# shelves_v05.net
KiCad netlist of a schematic drawn in EAGLE
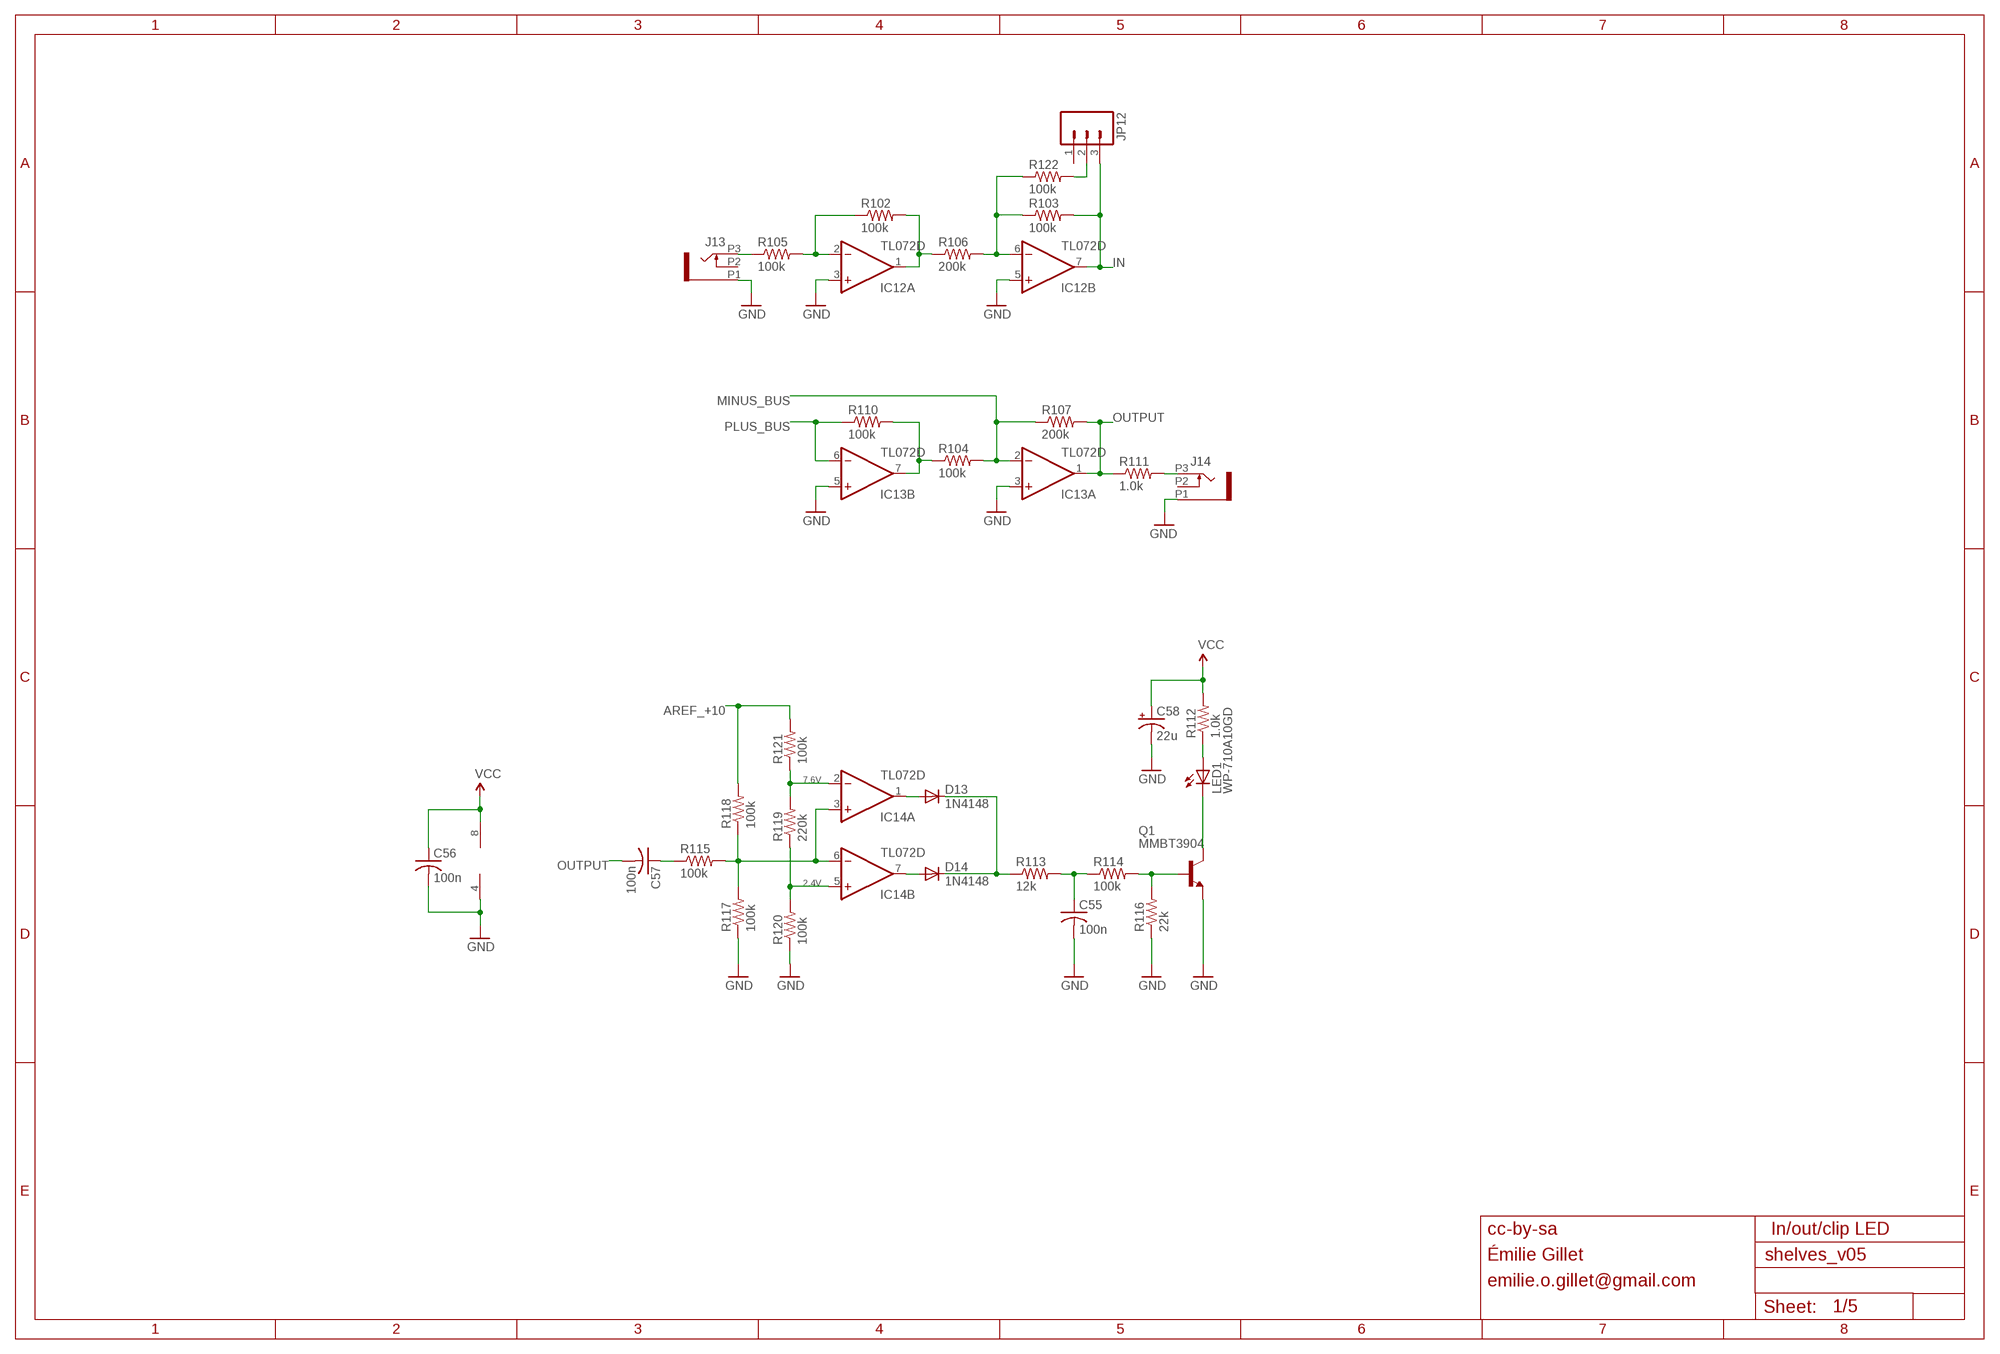
[diagram p0: schematic, sheet 1]
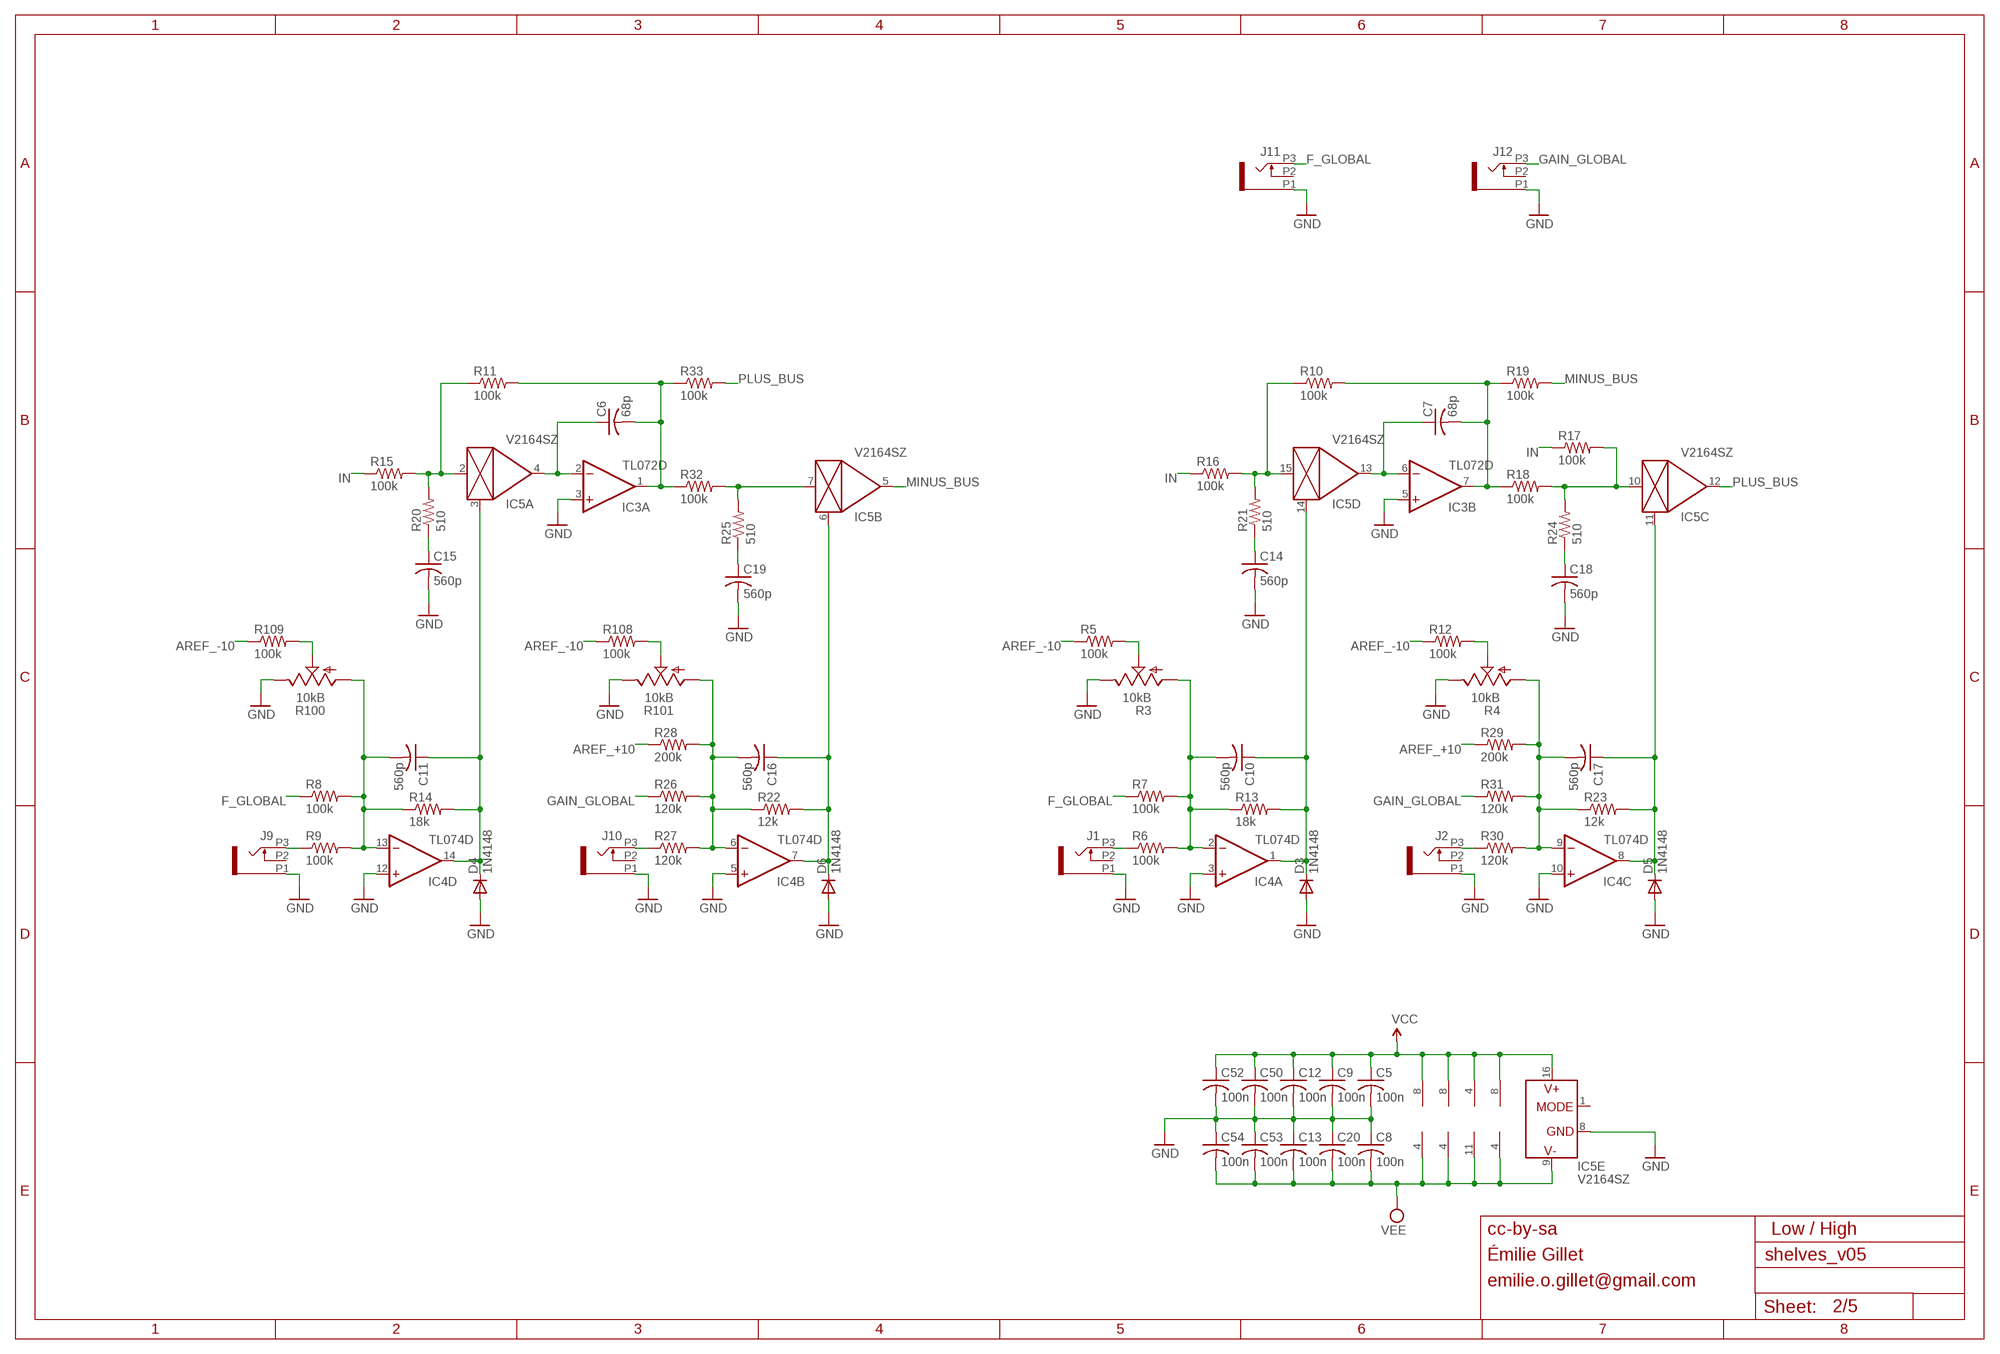
[diagram p1: schematic, sheet 2]
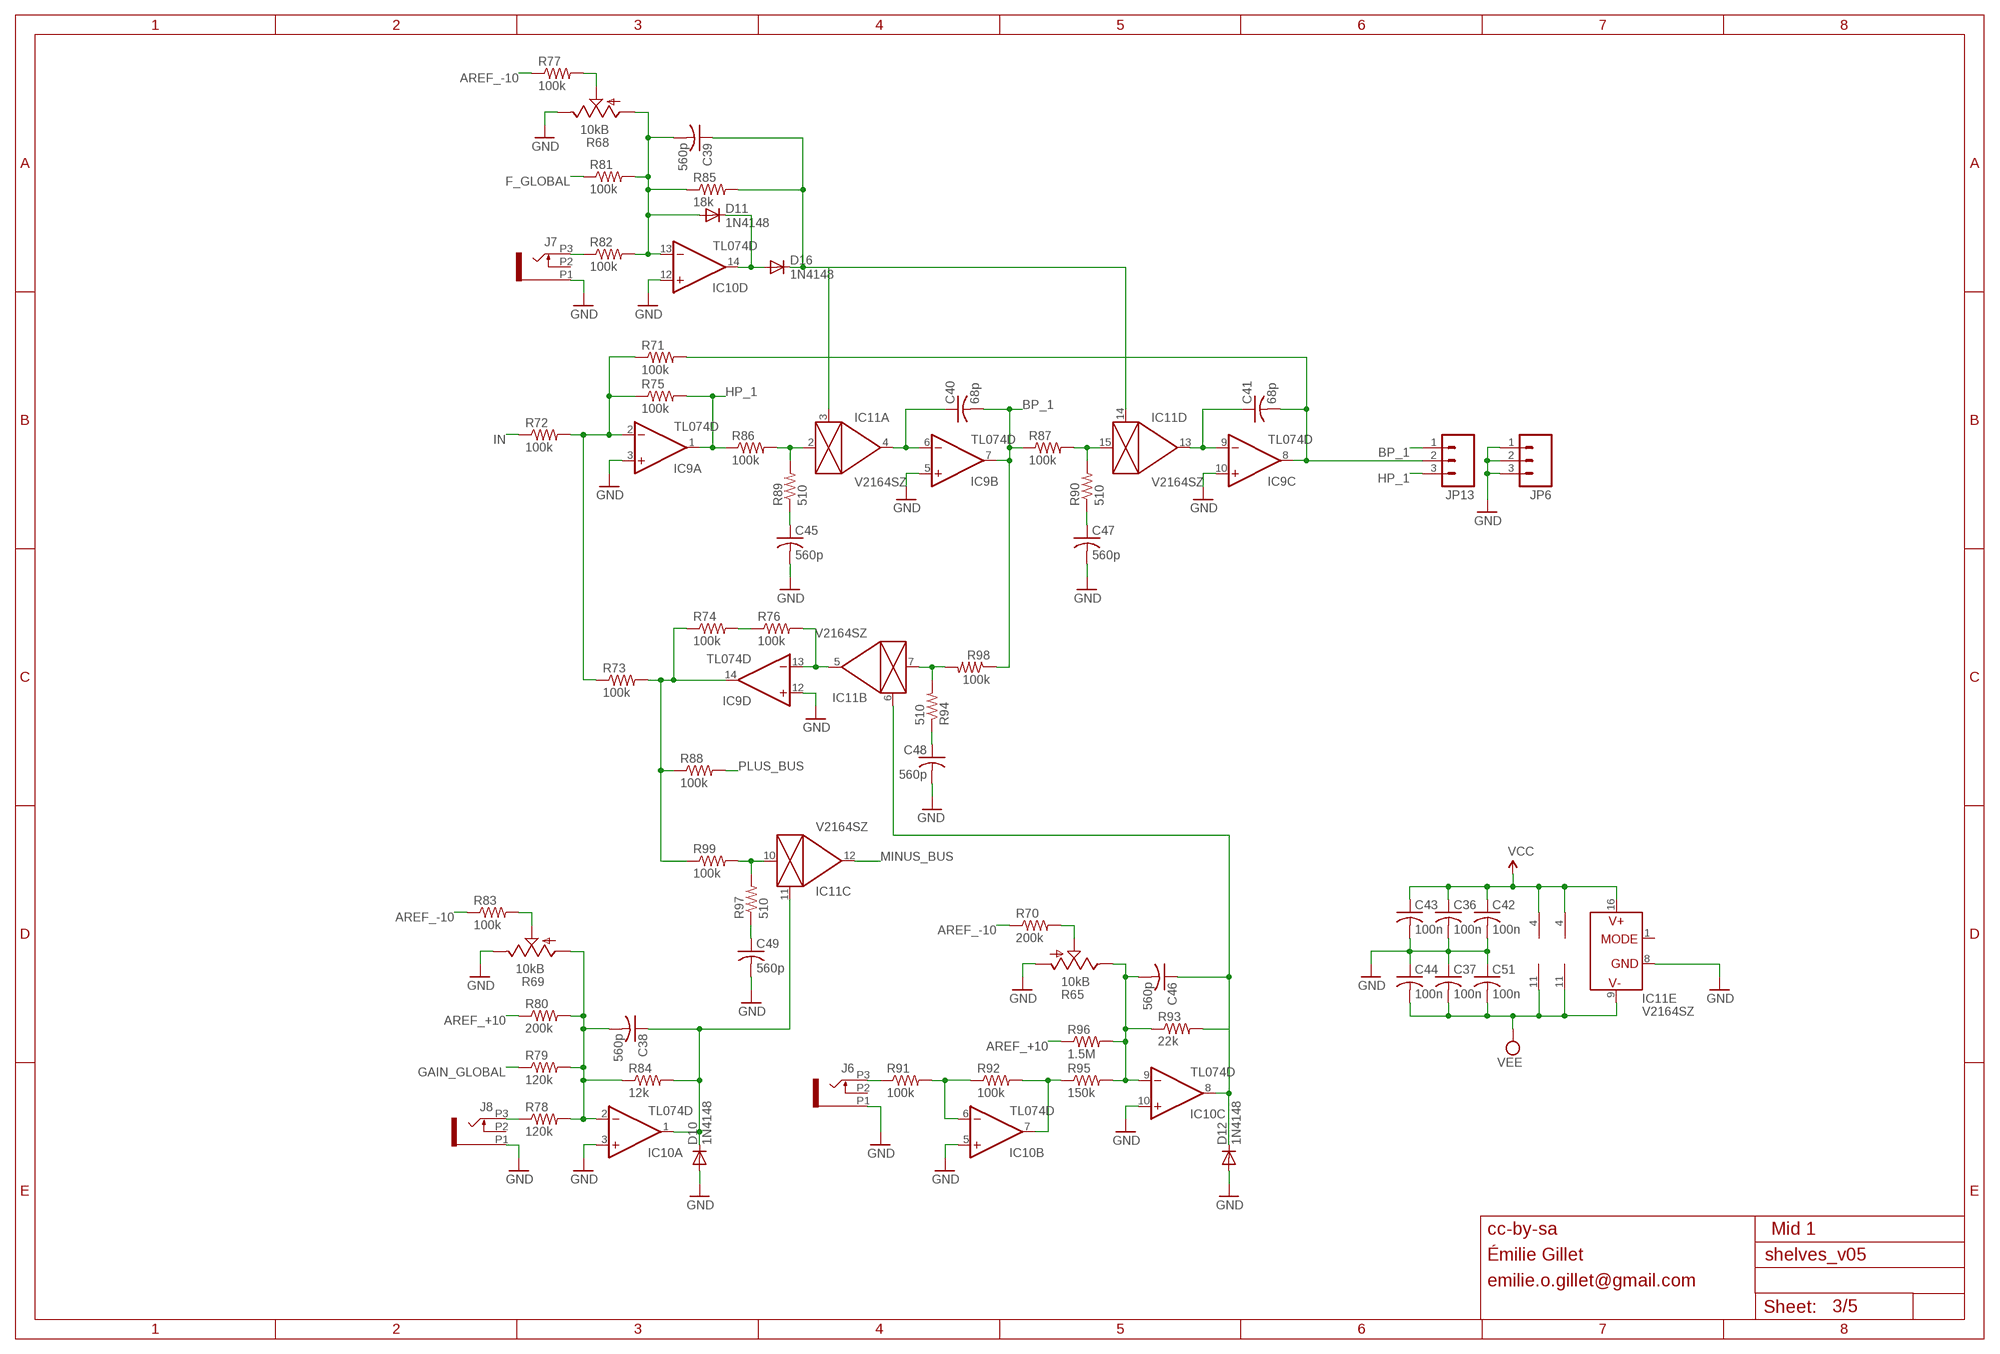
[diagram p2: schematic, sheet 3]
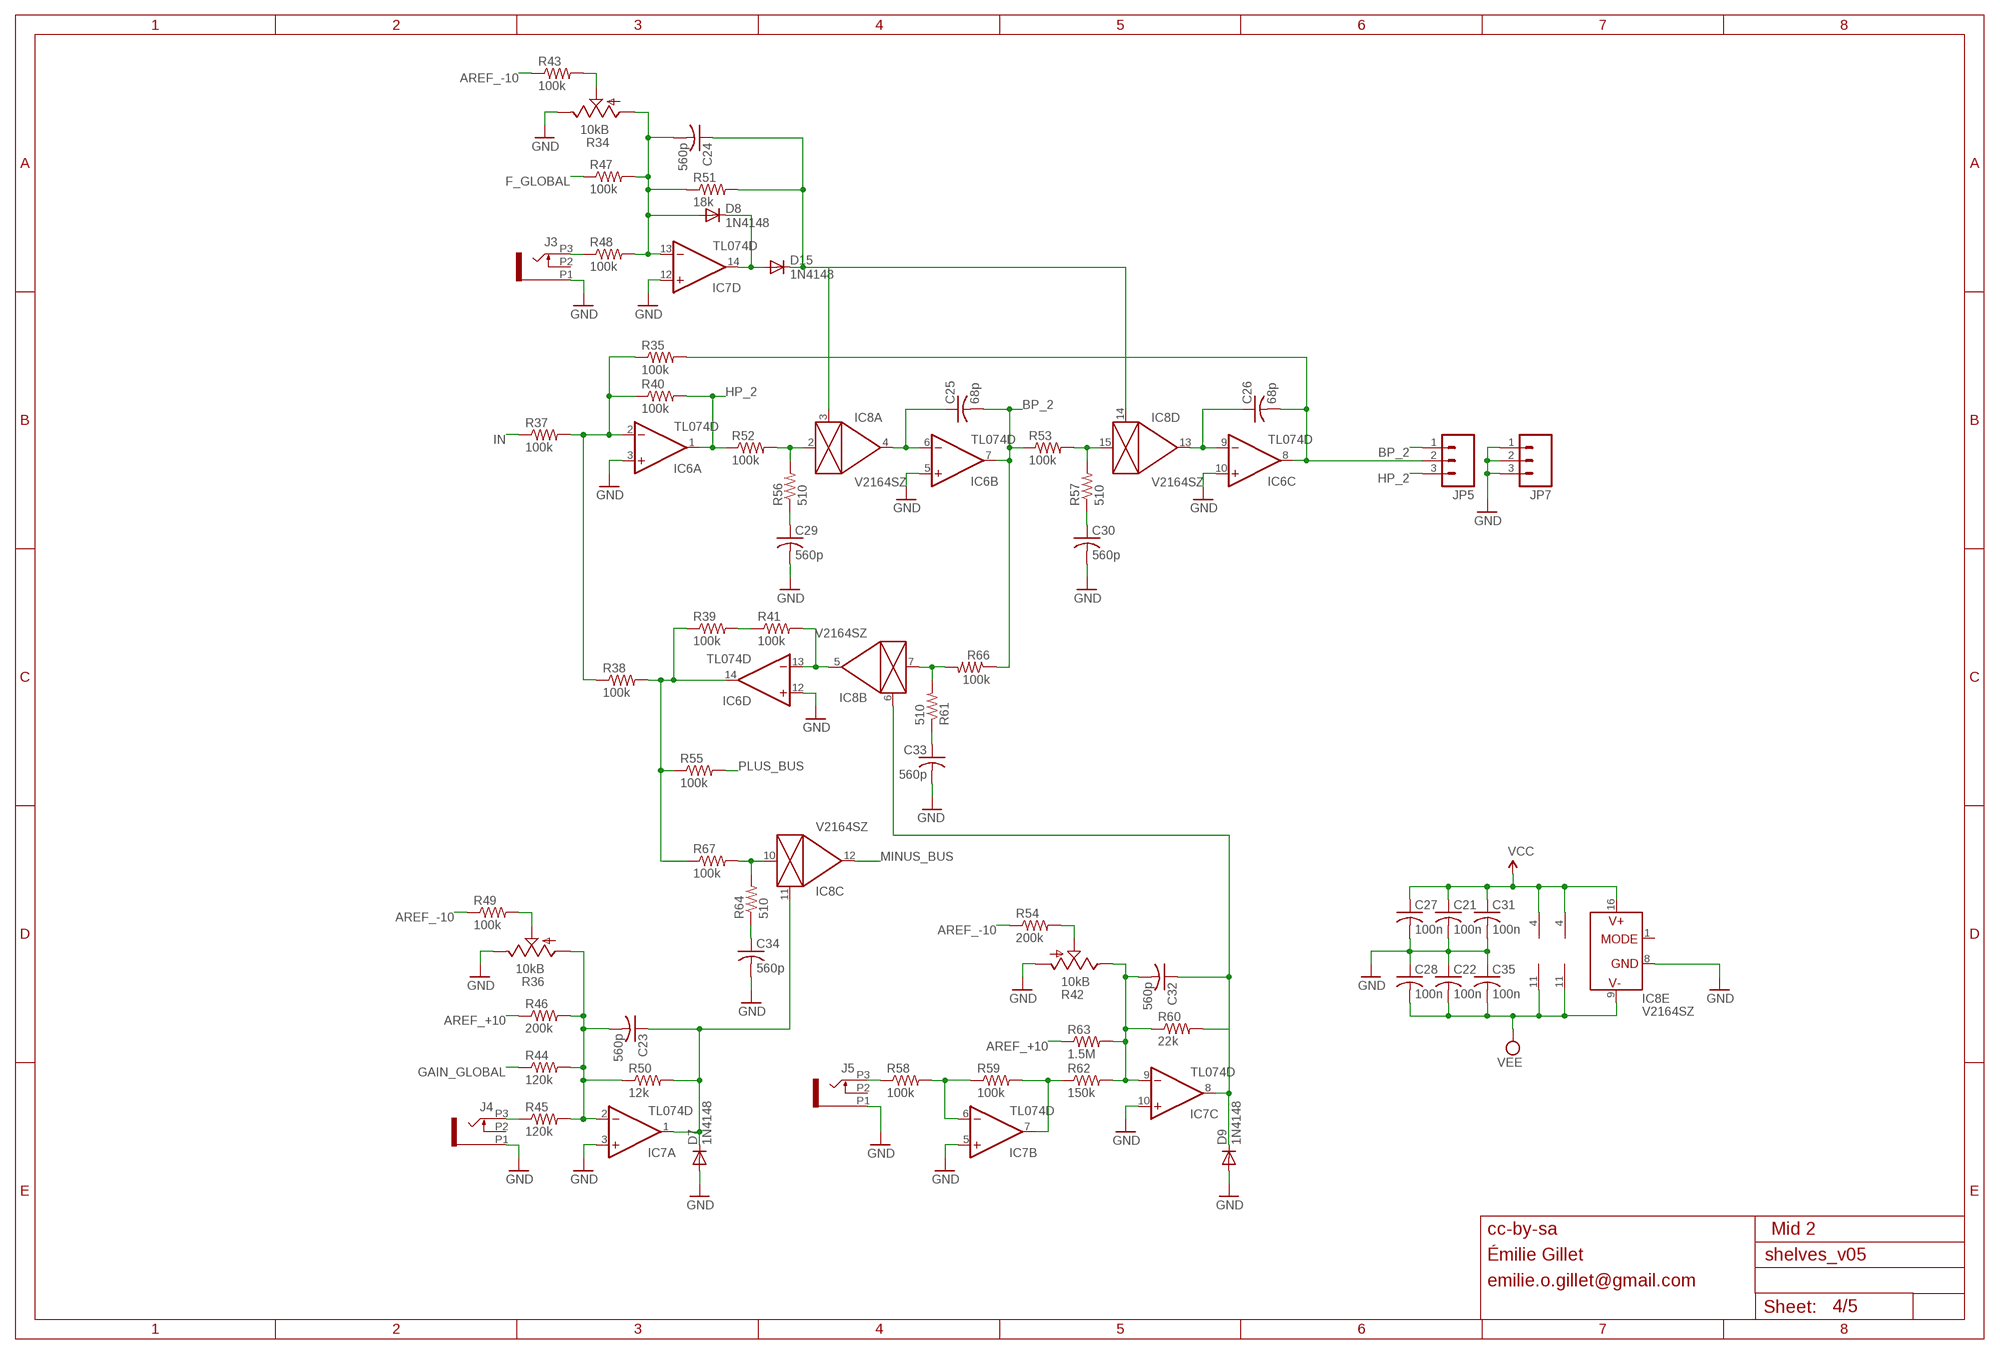
[diagram p3: schematic, sheet 4]
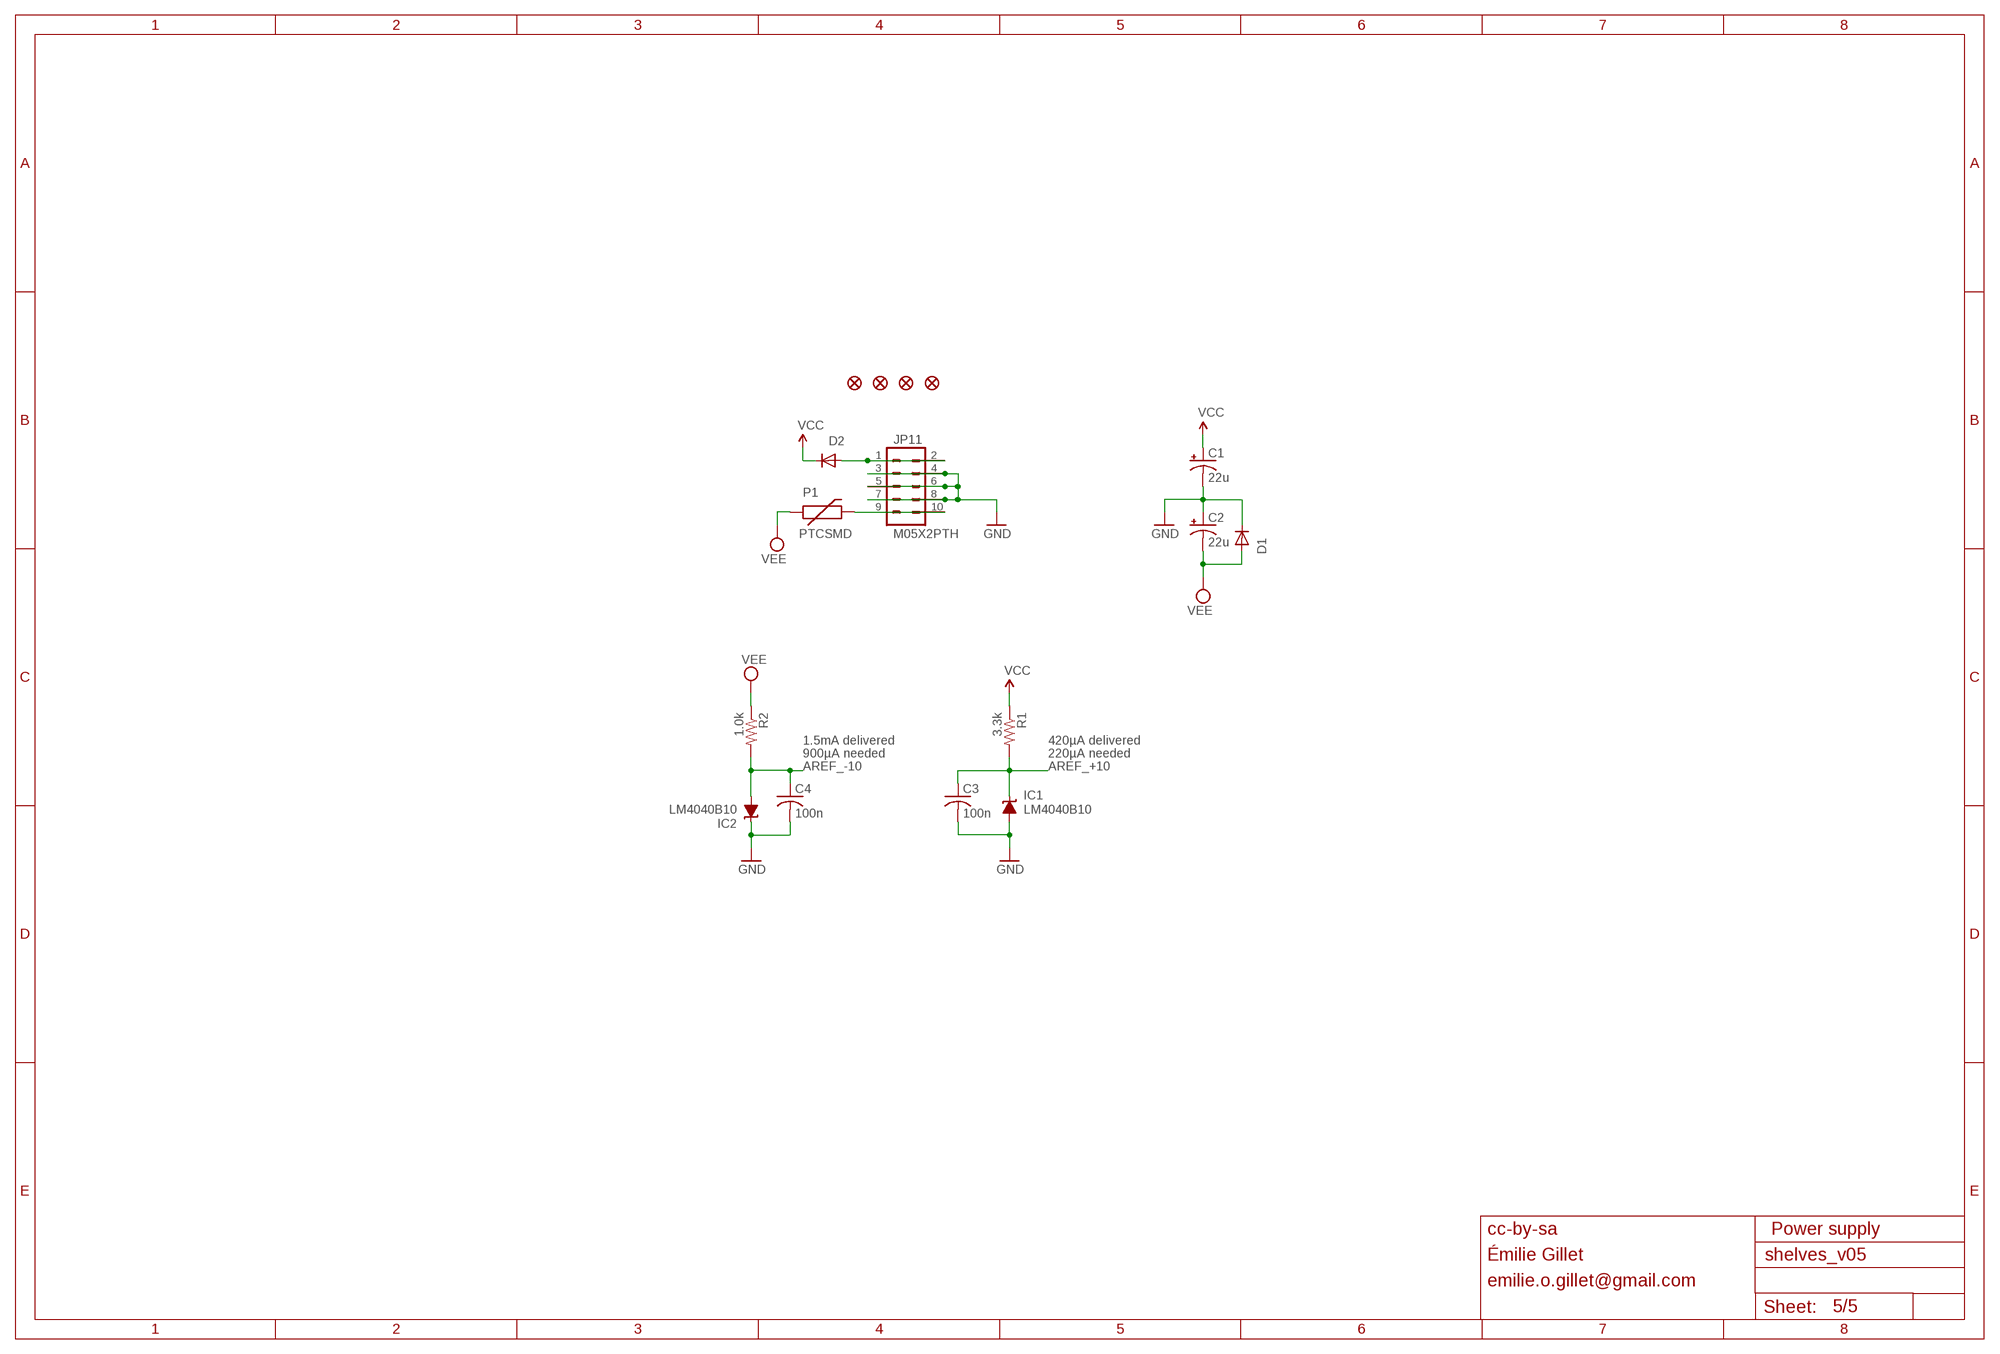
[diagram p4: schematic, sheet 5]

(export (version "E")
  (design (tool "Eeschema 10.0.6"))
  (components
    (comp (ref "C36")
      (value "100n")
      (footprint "eagle-import:C0603")
      (libsource (lib "eagle-import") (part "C-USC0603"))
    )
    (comp (ref "C37")
      (value "100n")
      (footprint "eagle-import:C0603")
      (libsource (lib "eagle-import") (part "C-USC0603"))
    )
    (comp (ref "C38")
      (value "560p")
      (footprint "eagle-import:C0603")
      (libsource (lib "eagle-import") (part "C-USC0603"))
    )
    (comp (ref "C39")
      (value "560p")
      (footprint "eagle-import:C0603")
      (libsource (lib "eagle-import") (part "C-USC0603"))
    )
    (comp (ref "C40")
      (value "68p")
      (footprint "eagle-import:C0603")
      (libsource (lib "eagle-import") (part "C-USC0603"))
    )
    (comp (ref "C41")
      (value "68p")
      (footprint "eagle-import:C0603")
      (libsource (lib "eagle-import") (part "C-USC0603"))
    )
    (comp (ref "C42")
      (value "100n")
      (footprint "eagle-import:C0603")
      (libsource (lib "eagle-import") (part "C-USC0603"))
    )
    (comp (ref "C43")
      (value "100n")
      (footprint "eagle-import:C0603")
      (libsource (lib "eagle-import") (part "C-USC0603"))
    )
    (comp (ref "C44")
      (value "100n")
      (footprint "eagle-import:C0603")
      (libsource (lib "eagle-import") (part "C-USC0603"))
    )
    (comp (ref "C45")
      (value "560p")
      (footprint "eagle-import:C0603")
      (libsource (lib "eagle-import") (part "C-USC0603"))
    )
    (comp (ref "C46")
      (value "560p")
      (footprint "eagle-import:C0603")
      (libsource (lib "eagle-import") (part "C-USC0603"))
    )
    (comp (ref "C47")
      (value "560p")
      (footprint "eagle-import:C0603")
      (libsource (lib "eagle-import") (part "C-USC0603"))
    )
    (comp (ref "C48")
      (value "560p")
      (footprint "eagle-import:C0603")
      (libsource (lib "eagle-import") (part "C-USC0603"))
    )
    (comp (ref "C49")
      (value "560p")
      (footprint "eagle-import:C0603")
      (libsource (lib "eagle-import") (part "C-USC0603"))
    )
    (comp (ref "C51")
      (value "100n")
      (footprint "eagle-import:C0603")
      (libsource (lib "eagle-import") (part "C-USC0603"))
    )
    (comp (ref "D10")
      (value "1N4148")
      (footprint "eagle-import:SOD323-W")
      (libsource (lib "eagle-import") (part "DIODE-SOD323-W"))
    )
    (comp (ref "D11")
      (value "1N4148")
      (footprint "eagle-import:SOD323-W")
      (libsource (lib "eagle-import") (part "DIODE-SOD323-W"))
    )
    (comp (ref "D12")
      (value "1N4148")
      (footprint "eagle-import:SOD323-W")
      (libsource (lib "eagle-import") (part "DIODE-SOD323-W"))
    )
    (comp (ref "D16")
      (value "1N4148")
      (footprint "eagle-import:SOD323-W")
      (libsource (lib "eagle-import") (part "DIODE-SOD323-W"))
    )
    (comp (ref "IC9")
      (value "TL074D")
      (footprint "eagle-import:SO14")
      (libsource (lib "eagle-import") (part "TL074D"))
    )
    (comp (ref "IC10")
      (value "TL074D")
      (footprint "eagle-import:SO14")
      (libsource (lib "eagle-import") (part "TL074D"))
    )
    (comp (ref "IC11")
      (value "V2164SZ")
      (footprint "eagle-import:SOIC16N")
      (libsource (lib "eagle-import") (part "SSM2164S"))
    )
    (comp (ref "J6")
      (value "PJ301_THONKICONN6")
      (footprint "eagle-import:WQP_PJ_301M6")
      (libsource (lib "eagle-import") (part "PJ301_THONKICONN6"))
    )
    (comp (ref "J7")
      (value "PJ301_THONKICONN6")
      (footprint "eagle-import:WQP_PJ_301M6")
      (libsource (lib "eagle-import") (part "PJ301_THONKICONN6"))
    )
    (comp (ref "J8")
      (value "PJ301_THONKICONN6")
      (footprint "eagle-import:WQP_PJ_301M6")
      (libsource (lib "eagle-import") (part "PJ301_THONKICONN6"))
    )
    (comp (ref "JP6")
      (value "M03PTH")
      (footprint "eagle-import:1X03")
      (libsource (lib "eagle-import") (part "M03PTH"))
    )
    (comp (ref "JP13")
      (value "M03PTH")
      (footprint "eagle-import:1X03")
      (libsource (lib "eagle-import") (part "M03PTH"))
    )
    (comp (ref "R65")
      (value "10kB")
      (footprint "eagle-import:ALPS_POT_VERTICAL")
      (libsource (lib "eagle-import") (part "POT_USVERTICAL"))
    )
    (comp (ref "R68")
      (value "10kB")
      (footprint "eagle-import:ALPS_POT_VERTICAL_PS")
      (libsource (lib "eagle-import") (part "POT_USVERTICAL_PS"))
    )
    (comp (ref "R69")
      (value "10kB")
      (footprint "eagle-import:ALPS_POT_VERTICAL_PS")
      (libsource (lib "eagle-import") (part "POT_USVERTICAL_PS"))
    )
    (comp (ref "R70")
      (value "200k")
      (footprint "eagle-import:R0603")
      (libsource (lib "eagle-import") (part "R-US_R0603"))
    )
    (comp (ref "R71")
      (value "100k")
      (footprint "eagle-import:R0603")
      (libsource (lib "eagle-import") (part "R-US_R0603"))
    )
    (comp (ref "R72")
      (value "100k")
      (footprint "eagle-import:R0603")
      (libsource (lib "eagle-import") (part "R-US_R0603"))
    )
    (comp (ref "R73")
      (value "100k")
      (footprint "eagle-import:R0603")
      (libsource (lib "eagle-import") (part "R-US_R0603"))
    )
    (comp (ref "R74")
      (value "100k")
      (footprint "eagle-import:R0603")
      (libsource (lib "eagle-import") (part "R-US_R0603"))
    )
    (comp (ref "R75")
      (value "100k")
      (footprint "eagle-import:R0603")
      (libsource (lib "eagle-import") (part "R-US_R0603"))
    )
    (comp (ref "R76")
      (value "100k")
      (footprint "eagle-import:R0603")
      (libsource (lib "eagle-import") (part "R-US_R0603"))
    )
    (comp (ref "R77")
      (value "100k")
      (footprint "eagle-import:R0603")
      (libsource (lib "eagle-import") (part "R-US_R0603"))
    )
    (comp (ref "R78")
      (value "120k")
      (footprint "eagle-import:R0603")
      (libsource (lib "eagle-import") (part "R-US_R0603"))
    )
    (comp (ref "R79")
      (value "120k")
      (footprint "eagle-import:R0603")
      (libsource (lib "eagle-import") (part "R-US_R0603"))
    )
    (comp (ref "R80")
      (value "200k")
      (footprint "eagle-import:R0603")
      (libsource (lib "eagle-import") (part "R-US_R0603"))
    )
    (comp (ref "R81")
      (value "100k")
      (footprint "eagle-import:R0603")
      (libsource (lib "eagle-import") (part "R-US_R0603"))
    )
    (comp (ref "R82")
      (value "100k")
      (footprint "eagle-import:R0603")
      (libsource (lib "eagle-import") (part "R-US_R0603"))
    )
    (comp (ref "R83")
      (value "100k")
      (footprint "eagle-import:R0603")
      (libsource (lib "eagle-import") (part "R-US_R0603"))
    )
    (comp (ref "R84")
      (value "12k")
      (footprint "eagle-import:R0603")
      (libsource (lib "eagle-import") (part "R-US_R0603"))
    )
    (comp (ref "R85")
      (value "18k")
      (footprint "eagle-import:R0603")
      (libsource (lib "eagle-import") (part "R-US_R0603"))
    )
    (comp (ref "R86")
      (value "100k")
      (footprint "eagle-import:R0603")
      (libsource (lib "eagle-import") (part "R-US_R0603"))
    )
    (comp (ref "R87")
      (value "100k")
      (footprint "eagle-import:R0603")
      (libsource (lib "eagle-import") (part "R-US_R0603"))
    )
    (comp (ref "R88")
      (value "100k")
      (footprint "eagle-import:R0603")
      (libsource (lib "eagle-import") (part "R-US_R0603"))
    )
    (comp (ref "R89")
      (value "510")
      (footprint "eagle-import:R0603")
      (libsource (lib "eagle-import") (part "R-US_R0603"))
    )
    (comp (ref "R90")
      (value "510")
      (footprint "eagle-import:R0603")
      (libsource (lib "eagle-import") (part "R-US_R0603"))
    )
    (comp (ref "R91")
      (value "100k")
      (footprint "eagle-import:R0603")
      (libsource (lib "eagle-import") (part "R-US_R0603"))
    )
    (comp (ref "R92")
      (value "100k")
      (footprint "eagle-import:R0603")
      (libsource (lib "eagle-import") (part "R-US_R0603"))
    )
    (comp (ref "R93")
      (value "22k")
      (footprint "eagle-import:R0603")
      (libsource (lib "eagle-import") (part "R-US_R0603"))
    )
    (comp (ref "R94")
      (value "510")
      (footprint "eagle-import:R0603")
      (libsource (lib "eagle-import") (part "R-US_R0603"))
    )
    (comp (ref "R95")
      (value "150k")
      (footprint "eagle-import:R0603")
      (libsource (lib "eagle-import") (part "R-US_R0603"))
    )
    (comp (ref "R96")
      (value "1.5M")
      (footprint "eagle-import:R0603")
      (libsource (lib "eagle-import") (part "R-US_R0603"))
    )
    (comp (ref "R97")
      (value "510")
      (footprint "eagle-import:R0603")
      (libsource (lib "eagle-import") (part "R-US_R0603"))
    )
    (comp (ref "R98")
      (value "100k")
      (footprint "eagle-import:R0603")
      (libsource (lib "eagle-import") (part "R-US_R0603"))
    )
    (comp (ref "R99")
      (value "100k")
      (footprint "eagle-import:R0603")
      (libsource (lib "eagle-import") (part "R-US_R0603"))
    )
    (comp (ref "C5")
      (value "100n")
      (footprint "eagle-import:C0603")
      (libsource (lib "eagle-import") (part "C-USC0603"))
    )
    (comp (ref "C6")
      (value "68p")
      (footprint "eagle-import:C0603")
      (libsource (lib "eagle-import") (part "C-USC0603"))
    )
    (comp (ref "C7")
      (value "68p")
      (footprint "eagle-import:C0603")
      (libsource (lib "eagle-import") (part "C-USC0603"))
    )
    (comp (ref "C8")
      (value "100n")
      (footprint "eagle-import:C0603")
      (libsource (lib "eagle-import") (part "C-USC0603"))
    )
    (comp (ref "C9")
      (value "100n")
      (footprint "eagle-import:C0603")
      (libsource (lib "eagle-import") (part "C-USC0603"))
    )
    (comp (ref "C10")
      (value "560p")
      (footprint "eagle-import:C0603")
      (libsource (lib "eagle-import") (part "C-USC0603"))
    )
    (comp (ref "C11")
      (value "560p")
      (footprint "eagle-import:C0603")
      (libsource (lib "eagle-import") (part "C-USC0603"))
    )
    (comp (ref "C12")
      (value "100n")
      (footprint "eagle-import:C0603")
      (libsource (lib "eagle-import") (part "C-USC0603"))
    )
    (comp (ref "C13")
      (value "100n")
      (footprint "eagle-import:C0603")
      (libsource (lib "eagle-import") (part "C-USC0603"))
    )
    (comp (ref "C14")
      (value "560p")
      (footprint "eagle-import:C0603")
      (libsource (lib "eagle-import") (part "C-USC0603"))
    )
    (comp (ref "C15")
      (value "560p")
      (footprint "eagle-import:C0603")
      (libsource (lib "eagle-import") (part "C-USC0603"))
    )
    (comp (ref "C16")
      (value "560p")
      (footprint "eagle-import:C0603")
      (libsource (lib "eagle-import") (part "C-USC0603"))
    )
    (comp (ref "C17")
      (value "560p")
      (footprint "eagle-import:C0603")
      (libsource (lib "eagle-import") (part "C-USC0603"))
    )
    (comp (ref "C18")
      (value "560p")
      (footprint "eagle-import:C0603")
      (libsource (lib "eagle-import") (part "C-USC0603"))
    )
    (comp (ref "C19")
      (value "560p")
      (footprint "eagle-import:C0603")
      (libsource (lib "eagle-import") (part "C-USC0603"))
    )
    (comp (ref "C20")
      (value "100n")
      (footprint "eagle-import:C0603")
      (libsource (lib "eagle-import") (part "C-USC0603"))
    )
    (comp (ref "C50")
      (value "100n")
      (footprint "eagle-import:C0603")
      (libsource (lib "eagle-import") (part "C-USC0603"))
    )
    (comp (ref "C52")
      (value "100n")
      (footprint "eagle-import:C0603")
      (libsource (lib "eagle-import") (part "C-USC0603"))
    )
    (comp (ref "C53")
      (value "100n")
      (footprint "eagle-import:C0603")
      (libsource (lib "eagle-import") (part "C-USC0603"))
    )
    (comp (ref "C54")
      (value "100n")
      (footprint "eagle-import:C0603")
      (libsource (lib "eagle-import") (part "C-USC0603"))
    )
    (comp (ref "D3")
      (value "1N4148")
      (footprint "eagle-import:SOD323-W")
      (libsource (lib "eagle-import") (part "DIODE-SOD323-W"))
    )
    (comp (ref "D4")
      (value "1N4148")
      (footprint "eagle-import:SOD323-W")
      (libsource (lib "eagle-import") (part "DIODE-SOD323-W"))
    )
    (comp (ref "D5")
      (value "1N4148")
      (footprint "eagle-import:SOD323-W")
      (libsource (lib "eagle-import") (part "DIODE-SOD323-W"))
    )
    (comp (ref "D6")
      (value "1N4148")
      (footprint "eagle-import:SOD323-W")
      (libsource (lib "eagle-import") (part "DIODE-SOD323-W"))
    )
    (comp (ref "IC3")
      (value "TL072D")
      (footprint "eagle-import:SO08")
      (libsource (lib "eagle-import") (part "TL072D"))
    )
    (comp (ref "IC4")
      (value "TL074D")
      (footprint "eagle-import:SO14")
      (libsource (lib "eagle-import") (part "TL074D"))
    )
    (comp (ref "IC5")
      (value "V2164SZ")
      (footprint "eagle-import:SOIC16N")
      (libsource (lib "eagle-import") (part "SSM2164S"))
    )
    (comp (ref "IC12")
      (value "TL072D")
      (footprint "eagle-import:SO08")
      (libsource (lib "eagle-import") (part "TL072D"))
    )
    (comp (ref "IC13")
      (value "TL072D")
      (footprint "eagle-import:SO08")
      (libsource (lib "eagle-import") (part "TL072D"))
    )
    (comp (ref "J1")
      (value "PJ301_THONKICONN6")
      (footprint "eagle-import:WQP_PJ_301M6")
      (libsource (lib "eagle-import") (part "PJ301_THONKICONN6"))
    )
    (comp (ref "J2")
      (value "PJ301_THONKICONN6")
      (footprint "eagle-import:WQP_PJ_301M6")
      (libsource (lib "eagle-import") (part "PJ301_THONKICONN6"))
    )
    (comp (ref "J9")
      (value "PJ301_THONKICONN6")
      (footprint "eagle-import:WQP_PJ_301M6")
      (libsource (lib "eagle-import") (part "PJ301_THONKICONN6"))
    )
    (comp (ref "J10")
      (value "PJ301_THONKICONN6")
      (footprint "eagle-import:WQP_PJ_301M6")
      (libsource (lib "eagle-import") (part "PJ301_THONKICONN6"))
    )
    (comp (ref "J11")
      (value "PJ301_THONKICONN6")
      (footprint "eagle-import:WQP_PJ_301M6")
      (libsource (lib "eagle-import") (part "PJ301_THONKICONN6"))
    )
    (comp (ref "J12")
      (value "PJ301_THONKICONN6")
      (footprint "eagle-import:WQP_PJ_301M6")
      (libsource (lib "eagle-import") (part "PJ301_THONKICONN6"))
    )
    (comp (ref "R3")
      (value "10kB")
      (footprint "eagle-import:ALPS_POT_VERTICAL_PS")
      (libsource (lib "eagle-import") (part "POT_USVERTICAL_PS"))
    )
    (comp (ref "R4")
      (value "10kB")
      (footprint "eagle-import:ALPS_POT_VERTICAL_PS")
      (libsource (lib "eagle-import") (part "POT_USVERTICAL_PS"))
    )
    (comp (ref "R5")
      (value "100k")
      (footprint "eagle-import:R0603")
      (libsource (lib "eagle-import") (part "R-US_R0603"))
    )
    (comp (ref "R6")
      (value "100k")
      (footprint "eagle-import:R0603")
      (libsource (lib "eagle-import") (part "R-US_R0603"))
    )
    (comp (ref "R7")
      (value "100k")
      (footprint "eagle-import:R0603")
      (libsource (lib "eagle-import") (part "R-US_R0603"))
    )
    (comp (ref "R8")
      (value "100k")
      (footprint "eagle-import:R0603")
      (libsource (lib "eagle-import") (part "R-US_R0603"))
    )
    (comp (ref "R9")
      (value "100k")
      (footprint "eagle-import:R0603")
      (libsource (lib "eagle-import") (part "R-US_R0603"))
    )
    (comp (ref "R10")
      (value "100k")
      (footprint "eagle-import:R0603")
      (libsource (lib "eagle-import") (part "R-US_R0603"))
    )
    (comp (ref "R11")
      (value "100k")
      (footprint "eagle-import:R0603")
      (libsource (lib "eagle-import") (part "R-US_R0603"))
    )
    (comp (ref "R12")
      (value "100k")
      (footprint "eagle-import:R0603")
      (libsource (lib "eagle-import") (part "R-US_R0603"))
    )
    (comp (ref "R13")
      (value "18k")
      (footprint "eagle-import:R0603")
      (libsource (lib "eagle-import") (part "R-US_R0603"))
    )
    (comp (ref "R14")
      (value "18k")
      (footprint "eagle-import:R0603")
      (libsource (lib "eagle-import") (part "R-US_R0603"))
    )
    (comp (ref "R15")
      (value "100k")
      (footprint "eagle-import:R0603")
      (libsource (lib "eagle-import") (part "R-US_R0603"))
    )
    (comp (ref "R16")
      (value "100k")
      (footprint "eagle-import:R0603")
      (libsource (lib "eagle-import") (part "R-US_R0603"))
    )
    (comp (ref "R17")
      (value "100k")
      (footprint "eagle-import:R0603")
      (libsource (lib "eagle-import") (part "R-US_R0603"))
    )
    (comp (ref "R18")
      (value "100k")
      (footprint "eagle-import:R0603")
      (libsource (lib "eagle-import") (part "R-US_R0603"))
    )
    (comp (ref "R19")
      (value "100k")
      (footprint "eagle-import:R0603")
      (libsource (lib "eagle-import") (part "R-US_R0603"))
    )
    (comp (ref "R20")
      (value "510")
      (footprint "eagle-import:R0603")
      (libsource (lib "eagle-import") (part "R-US_R0603"))
    )
    (comp (ref "R21")
      (value "510")
      (footprint "eagle-import:R0603")
      (libsource (lib "eagle-import") (part "R-US_R0603"))
    )
    (comp (ref "R22")
      (value "12k")
      (footprint "eagle-import:R0603")
      (libsource (lib "eagle-import") (part "R-US_R0603"))
    )
    (comp (ref "R23")
      (value "12k")
      (footprint "eagle-import:R0603")
      (libsource (lib "eagle-import") (part "R-US_R0603"))
    )
    (comp (ref "R24")
      (value "510")
      (footprint "eagle-import:R0603")
      (libsource (lib "eagle-import") (part "R-US_R0603"))
    )
    (comp (ref "R25")
      (value "510")
      (footprint "eagle-import:R0603")
      (libsource (lib "eagle-import") (part "R-US_R0603"))
    )
    (comp (ref "R26")
      (value "120k")
      (footprint "eagle-import:R0603")
      (libsource (lib "eagle-import") (part "R-US_R0603"))
    )
    (comp (ref "R27")
      (value "120k")
      (footprint "eagle-import:R0603")
      (libsource (lib "eagle-import") (part "R-US_R0603"))
    )
    (comp (ref "R28")
      (value "200k")
      (footprint "eagle-import:R0603")
      (libsource (lib "eagle-import") (part "R-US_R0603"))
    )
    (comp (ref "R29")
      (value "200k")
      (footprint "eagle-import:R0603")
      (libsource (lib "eagle-import") (part "R-US_R0603"))
    )
    (comp (ref "R30")
      (value "120k")
      (footprint "eagle-import:R0603")
      (libsource (lib "eagle-import") (part "R-US_R0603"))
    )
    (comp (ref "R31")
      (value "120k")
      (footprint "eagle-import:R0603")
      (libsource (lib "eagle-import") (part "R-US_R0603"))
    )
    (comp (ref "R32")
      (value "100k")
      (footprint "eagle-import:R0603")
      (libsource (lib "eagle-import") (part "R-US_R0603"))
    )
    (comp (ref "R33")
      (value "100k")
      (footprint "eagle-import:R0603")
      (libsource (lib "eagle-import") (part "R-US_R0603"))
    )
    (comp (ref "R100")
      (value "10kB")
      (footprint "eagle-import:ALPS_POT_VERTICAL_PS")
      (libsource (lib "eagle-import") (part "POT_USVERTICAL_PS"))
    )
    (comp (ref "R101")
      (value "10kB")
      (footprint "eagle-import:ALPS_POT_VERTICAL_PS")
      (libsource (lib "eagle-import") (part "POT_USVERTICAL_PS"))
    )
    (comp (ref "R108")
      (value "100k")
      (footprint "eagle-import:R0603")
      (libsource (lib "eagle-import") (part "R-US_R0603"))
    )
    (comp (ref "R109")
      (value "100k")
      (footprint "eagle-import:R0603")
      (libsource (lib "eagle-import") (part "R-US_R0603"))
    )
    (comp (ref "C1")
      (value "22u")
      (footprint "eagle-import:PANASONIC_C")
      (libsource (lib "eagle-import") (part "CPOL-USC"))
    )
    (comp (ref "C2")
      (value "22u")
      (footprint "eagle-import:PANASONIC_C")
      (libsource (lib "eagle-import") (part "CPOL-USC"))
    )
    (comp (ref "C3")
      (value "100n")
      (footprint "eagle-import:C0603")
      (libsource (lib "eagle-import") (part "C-USC0603"))
    )
    (comp (ref "C4")
      (value "100n")
      (footprint "eagle-import:C0603")
      (libsource (lib "eagle-import") (part "C-USC0603"))
    )
    (comp (ref "D1")
      (value "1N5819HW")
      (footprint "eagle-import:SOD123")
      (libsource (lib "eagle-import") (part "DIODE-SOD123"))
    )
    (comp (ref "D2")
      (value "1N5819HW")
      (footprint "eagle-import:SOD123")
      (libsource (lib "eagle-import") (part "DIODE-SOD123"))
    )
    (comp (ref "IC1")
      (value "LM4040B10")
      (footprint "eagle-import:DBZ_R-PDSO-G3")
      (libsource (lib "eagle-import") (part "LM4041DBZB12"))
    )
    (comp (ref "IC2")
      (value "LM4040B10")
      (footprint "eagle-import:DBZ_R-PDSO-G3")
      (libsource (lib "eagle-import") (part "LM4041DBZB12"))
    )
    (comp (ref "JP1")
      (value "FIDUCIAL1X2")
      (footprint "eagle-import:FIDUCIAL-1X2")
      (libsource (lib "eagle-import") (part "FIDUCIAL1X2"))
    )
    (comp (ref "JP2")
      (value "FIDUCIAL1X2")
      (footprint "eagle-import:FIDUCIAL-1X2")
      (libsource (lib "eagle-import") (part "FIDUCIAL1X2"))
    )
    (comp (ref "JP3")
      (value "FIDUCIAL1X2")
      (footprint "eagle-import:FIDUCIAL-1X2")
      (libsource (lib "eagle-import") (part "FIDUCIAL1X2"))
    )
    (comp (ref "JP4")
      (value "FIDUCIAL1X2")
      (footprint "eagle-import:FIDUCIAL-1X2")
      (libsource (lib "eagle-import") (part "FIDUCIAL1X2"))
    )
    (comp (ref "JP11")
      (value "M05X2PTH")
      (footprint "eagle-import:AVR_ICSP")
      (libsource (lib "eagle-import") (part "M05X2PTH"))
    )
    (comp (ref "P1")
      (value "PTCSMD")
      (footprint "eagle-import:PTC-1206")
      (libsource (lib "eagle-import") (part "PTCSMD"))
    )
    (comp (ref "R1")
      (value "3.3k")
      (footprint "eagle-import:R0603")
      (libsource (lib "eagle-import") (part "R-US_R0603"))
    )
    (comp (ref "R2")
      (value "1.0k")
      (footprint "eagle-import:R0603")
      (libsource (lib "eagle-import") (part "R-US_R0603"))
    )
    (comp (ref "C55")
      (value "100n")
      (footprint "eagle-import:C0603")
      (libsource (lib "eagle-import") (part "C-USC0603"))
    )
    (comp (ref "C56")
      (value "100n")
      (footprint "eagle-import:C0603")
      (libsource (lib "eagle-import") (part "C-USC0603"))
    )
    (comp (ref "C57")
      (value "100n")
      (footprint "eagle-import:C0603")
      (libsource (lib "eagle-import") (part "C-USC0603"))
    )
    (comp (ref "C58")
      (value "22u")
      (footprint "eagle-import:PANASONIC_C")
      (libsource (lib "eagle-import") (part "CPOL-USC"))
    )
    (comp (ref "D13")
      (value "1N4148")
      (footprint "eagle-import:SOD323-W")
      (libsource (lib "eagle-import") (part "DIODE-SOD323-W"))
    )
    (comp (ref "D14")
      (value "1N4148")
      (footprint "eagle-import:SOD323-W")
      (libsource (lib "eagle-import") (part "DIODE-SOD323-W"))
    )
    (comp (ref "IC14")
      (value "TL072D")
      (footprint "eagle-import:SO08")
      (libsource (lib "eagle-import") (part "TL072D"))
    )
    (comp (ref "J13")
      (value "PJ301_THONKICONN6")
      (footprint "eagle-import:WQP_PJ_301M6")
      (libsource (lib "eagle-import") (part "PJ301_THONKICONN6"))
    )
    (comp (ref "J14")
      (value "PJ301_THONKICONN6")
      (footprint "eagle-import:WQP_PJ_301M6")
      (libsource (lib "eagle-import") (part "PJ301_THONKICONN6"))
    )
    (comp (ref "JP12")
      (value "M03PTH")
      (footprint "eagle-import:1X03")
      (libsource (lib "eagle-import") (part "M03PTH"))
    )
    (comp (ref "LED1")
      (value "WP-710A10GD")
      (footprint "eagle-import:LED3MM")
      (libsource (lib "eagle-import") (part "LED3MM"))
    )
    (comp (ref "Q1")
      (value "MMBT3904")
      (footprint "eagle-import:SOT23-BEC")
      (libsource (lib "eagle-import") (part "-NPN-SOT23-BECMMBT3904LT1"))
    )
    (comp (ref "R102")
      (value "100k")
      (footprint "eagle-import:R0603")
      (libsource (lib "eagle-import") (part "R-US_R0603"))
    )
    (comp (ref "R103")
      (value "100k")
      (footprint "eagle-import:R0603")
      (libsource (lib "eagle-import") (part "R-US_R0603"))
    )
    (comp (ref "R104")
      (value "100k")
      (footprint "eagle-import:R0603")
      (libsource (lib "eagle-import") (part "R-US_R0603"))
    )
    (comp (ref "R105")
      (value "100k")
      (footprint "eagle-import:R0603")
      (libsource (lib "eagle-import") (part "R-US_R0603"))
    )
    (comp (ref "R106")
      (value "200k")
      (footprint "eagle-import:R0603")
      (libsource (lib "eagle-import") (part "R-US_R0603"))
    )
    (comp (ref "R107")
      (value "200k")
      (footprint "eagle-import:R0603")
      (libsource (lib "eagle-import") (part "R-US_R0603"))
    )
    (comp (ref "R110")
      (value "100k")
      (footprint "eagle-import:R0603")
      (libsource (lib "eagle-import") (part "R-US_R0603"))
    )
    (comp (ref "R111")
      (value "1.0k")
      (footprint "eagle-import:R0603")
      (libsource (lib "eagle-import") (part "R-US_R0603"))
    )
    (comp (ref "R112")
      (value "1.0k")
      (footprint "eagle-import:R0603")
      (libsource (lib "eagle-import") (part "R-US_R0603"))
    )
    (comp (ref "R113")
      (value "12k")
      (footprint "eagle-import:R0603")
      (libsource (lib "eagle-import") (part "R-US_R0603"))
    )
    (comp (ref "R114")
      (value "100k")
      (footprint "eagle-import:R0603")
      (libsource (lib "eagle-import") (part "R-US_R0603"))
    )
    (comp (ref "R115")
      (value "100k")
      (footprint "eagle-import:R0603")
      (libsource (lib "eagle-import") (part "R-US_R0603"))
    )
    (comp (ref "R116")
      (value "22k")
      (footprint "eagle-import:R0603")
      (libsource (lib "eagle-import") (part "R-US_R0603"))
    )
    (comp (ref "R117")
      (value "100k")
      (footprint "eagle-import:R0603")
      (libsource (lib "eagle-import") (part "R-US_R0603"))
    )
    (comp (ref "R118")
      (value "100k")
      (footprint "eagle-import:R0603")
      (libsource (lib "eagle-import") (part "R-US_R0603"))
    )
    (comp (ref "R119")
      (value "220k")
      (footprint "eagle-import:R0603")
      (libsource (lib "eagle-import") (part "R-US_R0603"))
    )
    (comp (ref "R120")
      (value "100k")
      (footprint "eagle-import:R0603")
      (libsource (lib "eagle-import") (part "R-US_R0603"))
    )
    (comp (ref "R121")
      (value "100k")
      (footprint "eagle-import:R0603")
      (libsource (lib "eagle-import") (part "R-US_R0603"))
    )
    (comp (ref "R122")
      (value "100k")
      (footprint "eagle-import:R0603")
      (libsource (lib "eagle-import") (part "R-US_R0603"))
    )
    (comp (ref "C21")
      (value "100n")
      (footprint "eagle-import:C0603")
      (libsource (lib "eagle-import") (part "C-USC0603"))
    )
    (comp (ref "C22")
      (value "100n")
      (footprint "eagle-import:C0603")
      (libsource (lib "eagle-import") (part "C-USC0603"))
    )
    (comp (ref "C23")
      (value "560p")
      (footprint "eagle-import:C0603")
      (libsource (lib "eagle-import") (part "C-USC0603"))
    )
    (comp (ref "C24")
      (value "560p")
      (footprint "eagle-import:C0603")
      (libsource (lib "eagle-import") (part "C-USC0603"))
    )
    (comp (ref "C25")
      (value "68p")
      (footprint "eagle-import:C0603")
      (libsource (lib "eagle-import") (part "C-USC0603"))
    )
    (comp (ref "C26")
      (value "68p")
      (footprint "eagle-import:C0603")
      (libsource (lib "eagle-import") (part "C-USC0603"))
    )
    (comp (ref "C27")
      (value "100n")
      (footprint "eagle-import:C0603")
      (libsource (lib "eagle-import") (part "C-USC0603"))
    )
    (comp (ref "C28")
      (value "100n")
      (footprint "eagle-import:C0603")
      (libsource (lib "eagle-import") (part "C-USC0603"))
    )
    (comp (ref "C29")
      (value "560p")
      (footprint "eagle-import:C0603")
      (libsource (lib "eagle-import") (part "C-USC0603"))
    )
    (comp (ref "C30")
      (value "560p")
      (footprint "eagle-import:C0603")
      (libsource (lib "eagle-import") (part "C-USC0603"))
    )
    (comp (ref "C31")
      (value "100n")
      (footprint "eagle-import:C0603")
      (libsource (lib "eagle-import") (part "C-USC0603"))
    )
    (comp (ref "C32")
      (value "560p")
      (footprint "eagle-import:C0603")
      (libsource (lib "eagle-import") (part "C-USC0603"))
    )
    (comp (ref "C33")
      (value "560p")
      (footprint "eagle-import:C0603")
      (libsource (lib "eagle-import") (part "C-USC0603"))
    )
    (comp (ref "C34")
      (value "560p")
      (footprint "eagle-import:C0603")
      (libsource (lib "eagle-import") (part "C-USC0603"))
    )
    (comp (ref "C35")
      (value "100n")
      (footprint "eagle-import:C0603")
      (libsource (lib "eagle-import") (part "C-USC0603"))
    )
    (comp (ref "D7")
      (value "1N4148")
      (footprint "eagle-import:SOD323-W")
      (libsource (lib "eagle-import") (part "DIODE-SOD323-W"))
    )
    (comp (ref "D8")
      (value "1N4148")
      (footprint "eagle-import:SOD323-W")
      (libsource (lib "eagle-import") (part "DIODE-SOD323-W"))
    )
    (comp (ref "D9")
      (value "1N4148")
      (footprint "eagle-import:SOD323-W")
      (libsource (lib "eagle-import") (part "DIODE-SOD323-W"))
    )
    (comp (ref "D15")
      (value "1N4148")
      (footprint "eagle-import:SOD323-W")
      (libsource (lib "eagle-import") (part "DIODE-SOD323-W"))
    )
    (comp (ref "IC6")
      (value "TL074D")
      (footprint "eagle-import:SO14")
      (libsource (lib "eagle-import") (part "TL074D"))
    )
    (comp (ref "IC7")
      (value "TL074D")
      (footprint "eagle-import:SO14")
      (libsource (lib "eagle-import") (part "TL074D"))
    )
    (comp (ref "IC8")
      (value "V2164SZ")
      (footprint "eagle-import:SOIC16N")
      (libsource (lib "eagle-import") (part "SSM2164S"))
    )
    (comp (ref "J3")
      (value "PJ301_THONKICONN6")
      (footprint "eagle-import:WQP_PJ_301M6")
      (libsource (lib "eagle-import") (part "PJ301_THONKICONN6"))
    )
    (comp (ref "J4")
      (value "PJ301_THONKICONN6")
      (footprint "eagle-import:WQP_PJ_301M6")
      (libsource (lib "eagle-import") (part "PJ301_THONKICONN6"))
    )
    (comp (ref "J5")
      (value "PJ301_THONKICONN6")
      (footprint "eagle-import:WQP_PJ_301M6")
      (libsource (lib "eagle-import") (part "PJ301_THONKICONN6"))
    )
    (comp (ref "JP5")
      (value "M03PTH")
      (footprint "eagle-import:1X03")
      (libsource (lib "eagle-import") (part "M03PTH"))
    )
    (comp (ref "JP7")
      (value "M03PTH")
      (footprint "eagle-import:1X03")
      (libsource (lib "eagle-import") (part "M03PTH"))
    )
    (comp (ref "R34")
      (value "10kB")
      (footprint "eagle-import:ALPS_POT_VERTICAL_PS")
      (libsource (lib "eagle-import") (part "POT_USVERTICAL_PS"))
    )
    (comp (ref "R35")
      (value "100k")
      (footprint "eagle-import:R0603")
      (libsource (lib "eagle-import") (part "R-US_R0603"))
    )
    (comp (ref "R36")
      (value "10kB")
      (footprint "eagle-import:ALPS_POT_VERTICAL_PS")
      (libsource (lib "eagle-import") (part "POT_USVERTICAL_PS"))
    )
    (comp (ref "R37")
      (value "100k")
      (footprint "eagle-import:R0603")
      (libsource (lib "eagle-import") (part "R-US_R0603"))
    )
    (comp (ref "R38")
      (value "100k")
      (footprint "eagle-import:R0603")
      (libsource (lib "eagle-import") (part "R-US_R0603"))
    )
    (comp (ref "R39")
      (value "100k")
      (footprint "eagle-import:R0603")
      (libsource (lib "eagle-import") (part "R-US_R0603"))
    )
    (comp (ref "R40")
      (value "100k")
      (footprint "eagle-import:R0603")
      (libsource (lib "eagle-import") (part "R-US_R0603"))
    )
    (comp (ref "R41")
      (value "100k")
      (footprint "eagle-import:R0603")
      (libsource (lib "eagle-import") (part "R-US_R0603"))
    )
    (comp (ref "R42")
      (value "10kB")
      (footprint "eagle-import:ALPS_POT_VERTICAL")
      (libsource (lib "eagle-import") (part "POT_USVERTICAL"))
    )
    (comp (ref "R43")
      (value "100k")
      (footprint "eagle-import:R0603")
      (libsource (lib "eagle-import") (part "R-US_R0603"))
    )
    (comp (ref "R44")
      (value "120k")
      (footprint "eagle-import:R0603")
      (libsource (lib "eagle-import") (part "R-US_R0603"))
    )
    (comp (ref "R45")
      (value "120k")
      (footprint "eagle-import:R0603")
      (libsource (lib "eagle-import") (part "R-US_R0603"))
    )
    (comp (ref "R46")
      (value "200k")
      (footprint "eagle-import:R0603")
      (libsource (lib "eagle-import") (part "R-US_R0603"))
    )
    (comp (ref "R47")
      (value "100k")
      (footprint "eagle-import:R0603")
      (libsource (lib "eagle-import") (part "R-US_R0603"))
    )
    (comp (ref "R48")
      (value "100k")
      (footprint "eagle-import:R0603")
      (libsource (lib "eagle-import") (part "R-US_R0603"))
    )
    (comp (ref "R49")
      (value "100k")
      (footprint "eagle-import:R0603")
      (libsource (lib "eagle-import") (part "R-US_R0603"))
    )
    (comp (ref "R50")
      (value "12k")
      (footprint "eagle-import:R0603")
      (libsource (lib "eagle-import") (part "R-US_R0603"))
    )
    (comp (ref "R51")
      (value "18k")
      (footprint "eagle-import:R0603")
      (libsource (lib "eagle-import") (part "R-US_R0603"))
    )
    (comp (ref "R52")
      (value "100k")
      (footprint "eagle-import:R0603")
      (libsource (lib "eagle-import") (part "R-US_R0603"))
    )
    (comp (ref "R53")
      (value "100k")
      (footprint "eagle-import:R0603")
      (libsource (lib "eagle-import") (part "R-US_R0603"))
    )
    (comp (ref "R54")
      (value "200k")
      (footprint "eagle-import:R0603")
      (libsource (lib "eagle-import") (part "R-US_R0603"))
    )
    (comp (ref "R55")
      (value "100k")
      (footprint "eagle-import:R0603")
      (libsource (lib "eagle-import") (part "R-US_R0603"))
    )
    (comp (ref "R56")
      (value "510")
      (footprint "eagle-import:R0603")
      (libsource (lib "eagle-import") (part "R-US_R0603"))
    )
    (comp (ref "R57")
      (value "510")
      (footprint "eagle-import:R0603")
      (libsource (lib "eagle-import") (part "R-US_R0603"))
    )
    (comp (ref "R58")
      (value "100k")
      (footprint "eagle-import:R0603")
      (libsource (lib "eagle-import") (part "R-US_R0603"))
    )
    (comp (ref "R59")
      (value "100k")
      (footprint "eagle-import:R0603")
      (libsource (lib "eagle-import") (part "R-US_R0603"))
    )
    (comp (ref "R60")
      (value "22k")
      (footprint "eagle-import:R0603")
      (libsource (lib "eagle-import") (part "R-US_R0603"))
    )
    (comp (ref "R61")
      (value "510")
      (footprint "eagle-import:R0603")
      (libsource (lib "eagle-import") (part "R-US_R0603"))
    )
    (comp (ref "R62")
      (value "150k")
      (footprint "eagle-import:R0603")
      (libsource (lib "eagle-import") (part "R-US_R0603"))
    )
    (comp (ref "R63")
      (value "1.5M")
      (footprint "eagle-import:R0603")
      (libsource (lib "eagle-import") (part "R-US_R0603"))
    )
    (comp (ref "R64")
      (value "510")
      (footprint "eagle-import:R0603")
      (libsource (lib "eagle-import") (part "R-US_R0603"))
    )
    (comp (ref "R66")
      (value "100k")
      (footprint "eagle-import:R0603")
      (libsource (lib "eagle-import") (part "R-US_R0603"))
    )
    (comp (ref "R67")
      (value "100k")
      (footprint "eagle-import:R0603")
      (libsource (lib "eagle-import") (part "R-US_R0603"))
    )
  )
  (nets
    (net (code "1") (name "AREF_+10") (class "Default")
      (node (ref "C3") (pin "1") (pinfunction "1_1") (pintype "passive"))
      (node (ref "IC1") (pin "1") (pinfunction "C_1") (pintype "passive"))
      (node (ref "R1") (pin "2") (pinfunction "2_2") (pintype "passive"))
      (node (ref "R118") (pin "2") (pinfunction "2_2") (pintype "passive"))
      (node (ref "R121") (pin "2") (pinfunction "2_2") (pintype "passive"))
      (node (ref "R28") (pin "1") (pinfunction "1_1") (pintype "passive"))
      (node (ref "R29") (pin "1") (pinfunction "1_1") (pintype "passive"))
      (node (ref "R46") (pin "1") (pinfunction "1_1") (pintype "passive"))
      (node (ref "R63") (pin "1") (pinfunction "1_1") (pintype "passive"))
      (node (ref "R80") (pin "1") (pinfunction "1_1") (pintype "passive"))
      (node (ref "R96") (pin "1") (pinfunction "1_1") (pintype "passive"))
    )
    (net (code "2") (name "AREF_-10") (class "Default")
      (node (ref "C4") (pin "1") (pinfunction "1_1") (pintype "passive"))
      (node (ref "IC2") (pin "2") (pinfunction "A_2") (pintype "passive"))
      (node (ref "R108") (pin "1") (pinfunction "1_1") (pintype "passive"))
      (node (ref "R109") (pin "1") (pinfunction "1_1") (pintype "passive"))
      (node (ref "R12") (pin "1") (pinfunction "1_1") (pintype "passive"))
      (node (ref "R2") (pin "2") (pinfunction "2_2") (pintype "passive"))
      (node (ref "R43") (pin "1") (pinfunction "1_1") (pintype "passive"))
      (node (ref "R49") (pin "1") (pinfunction "1_1") (pintype "passive"))
      (node (ref "R5") (pin "1") (pinfunction "1_1") (pintype "passive"))
      (node (ref "R54") (pin "1") (pinfunction "1_1") (pintype "passive"))
      (node (ref "R70") (pin "1") (pinfunction "1_1") (pintype "passive"))
      (node (ref "R77") (pin "1") (pinfunction "1_1") (pintype "passive"))
      (node (ref "R83") (pin "1") (pinfunction "1_1") (pintype "passive"))
    )
    (net (code "3") (name "BP_1") (class "Default")
      (node (ref "C40") (pin "2") (pinfunction "2_2") (pintype "passive"))
      (node (ref "IC9") (pin "7") (pinfunction "OUT_7") (pintype "output"))
      (node (ref "JP13") (pin "1") (pinfunction "1_1") (pintype "passive"))
      (node (ref "R87") (pin "1") (pinfunction "1_1") (pintype "passive"))
      (node (ref "R98") (pin "1") (pinfunction "1_1") (pintype "passive"))
    )
    (net (code "4") (name "BP_2") (class "Default")
      (node (ref "C25") (pin "2") (pinfunction "2_2") (pintype "passive"))
      (node (ref "IC6") (pin "7") (pinfunction "OUT_7") (pintype "output"))
      (node (ref "JP5") (pin "1") (pinfunction "1_1") (pintype "passive"))
      (node (ref "R53") (pin "1") (pinfunction "1_1") (pintype "passive"))
      (node (ref "R66") (pin "1") (pinfunction "1_1") (pintype "passive"))
    )
    (net (code "5") (name "F_GLOBAL") (class "Default")
      (node (ref "J11") (pin "P3") (pinfunction "3_P3") (pintype "passive"))
      (node (ref "R47") (pin "1") (pinfunction "1_1") (pintype "passive"))
      (node (ref "R7") (pin "1") (pinfunction "1_1") (pintype "passive"))
      (node (ref "R8") (pin "1") (pinfunction "1_1") (pintype "passive"))
      (node (ref "R81") (pin "1") (pinfunction "1_1") (pintype "passive"))
    )
    (net (code "6") (name "GAIN_GLOBAL") (class "Default")
      (node (ref "J12") (pin "P3") (pinfunction "3_P3") (pintype "passive"))
      (node (ref "R26") (pin "1") (pinfunction "1_1") (pintype "passive"))
      (node (ref "R31") (pin "1") (pinfunction "1_1") (pintype "passive"))
      (node (ref "R44") (pin "1") (pinfunction "1_1") (pintype "passive"))
      (node (ref "R79") (pin "1") (pinfunction "1_1") (pintype "passive"))
    )
    (net (code "7") (name "GND") (class "Default")
      (node (ref "C1") (pin "-") (pinfunction "-_-") (pintype "passive"))
      (node (ref "C12") (pin "2") (pinfunction "2_2") (pintype "passive"))
      (node (ref "C13") (pin "1") (pinfunction "1_1") (pintype "passive"))
      (node (ref "C14") (pin "2") (pinfunction "2_2") (pintype "passive"))
      (node (ref "C15") (pin "2") (pinfunction "2_2") (pintype "passive"))
      (node (ref "C18") (pin "2") (pinfunction "2_2") (pintype "passive"))
      (node (ref "C19") (pin "2") (pinfunction "2_2") (pintype "passive"))
      (node (ref "C2") (pin "+") (pinfunction "+_+") (pintype "passive"))
      (node (ref "C20") (pin "1") (pinfunction "1_1") (pintype "passive"))
      (node (ref "C21") (pin "2") (pinfunction "2_2") (pintype "passive"))
      (node (ref "C22") (pin "1") (pinfunction "1_1") (pintype "passive"))
      (node (ref "C27") (pin "2") (pinfunction "2_2") (pintype "passive"))
      (node (ref "C28") (pin "1") (pinfunction "1_1") (pintype "passive"))
      (node (ref "C29") (pin "2") (pinfunction "2_2") (pintype "passive"))
      (node (ref "C3") (pin "2") (pinfunction "2_2") (pintype "passive"))
      (node (ref "C30") (pin "2") (pinfunction "2_2") (pintype "passive"))
      (node (ref "C31") (pin "2") (pinfunction "2_2") (pintype "passive"))
      (node (ref "C33") (pin "2") (pinfunction "2_2") (pintype "passive"))
      (node (ref "C34") (pin "2") (pinfunction "2_2") (pintype "passive"))
      (node (ref "C35") (pin "1") (pinfunction "1_1") (pintype "passive"))
      (node (ref "C36") (pin "2") (pinfunction "2_2") (pintype "passive"))
      (node (ref "C37") (pin "1") (pinfunction "1_1") (pintype "passive"))
      (node (ref "C4") (pin "2") (pinfunction "2_2") (pintype "passive"))
      (node (ref "C42") (pin "2") (pinfunction "2_2") (pintype "passive"))
      (node (ref "C43") (pin "2") (pinfunction "2_2") (pintype "passive"))
      (node (ref "C44") (pin "1") (pinfunction "1_1") (pintype "passive"))
      (node (ref "C45") (pin "2") (pinfunction "2_2") (pintype "passive"))
      (node (ref "C47") (pin "2") (pinfunction "2_2") (pintype "passive"))
      (node (ref "C48") (pin "2") (pinfunction "2_2") (pintype "passive"))
      (node (ref "C49") (pin "2") (pinfunction "2_2") (pintype "passive"))
      (node (ref "C5") (pin "2") (pinfunction "2_2") (pintype "passive"))
      (node (ref "C50") (pin "2") (pinfunction "2_2") (pintype "passive"))
      (node (ref "C51") (pin "1") (pinfunction "1_1") (pintype "passive"))
      (node (ref "C52") (pin "2") (pinfunction "2_2") (pintype "passive"))
      (node (ref "C53") (pin "1") (pinfunction "1_1") (pintype "passive"))
      (node (ref "C54") (pin "1") (pinfunction "1_1") (pintype "passive"))
      (node (ref "C55") (pin "2") (pinfunction "2_2") (pintype "passive"))
      (node (ref "C56") (pin "2") (pinfunction "2_2") (pintype "passive"))
      (node (ref "C58") (pin "-") (pinfunction "-_-") (pintype "passive"))
      (node (ref "C8") (pin "1") (pinfunction "1_1") (pintype "passive"))
      (node (ref "C9") (pin "2") (pinfunction "2_2") (pintype "passive"))
      (node (ref "D1") (pin "C") (pinfunction "C_C") (pintype "passive"))
      (node (ref "D10") (pin "A") (pinfunction "A_A") (pintype "passive"))
      (node (ref "D12") (pin "A") (pinfunction "A_A") (pintype "passive"))
      (node (ref "D3") (pin "A") (pinfunction "A_A") (pintype "passive"))
      (node (ref "D4") (pin "A") (pinfunction "A_A") (pintype "passive"))
      (node (ref "D5") (pin "A") (pinfunction "A_A") (pintype "passive"))
      (node (ref "D6") (pin "A") (pinfunction "A_A") (pintype "passive"))
      (node (ref "D7") (pin "A") (pinfunction "A_A") (pintype "passive"))
      (node (ref "D9") (pin "A") (pinfunction "A_A") (pintype "passive"))
      (node (ref "IC1") (pin "2") (pinfunction "A_2") (pintype "passive"))
      (node (ref "IC10") (pin "10") (pinfunction "+IN_10") (pintype "input"))
      (node (ref "IC10") (pin "12") (pinfunction "+IN_12") (pintype "input"))
      (node (ref "IC10") (pin "3") (pinfunction "+IN_3") (pintype "input"))
      (node (ref "IC10") (pin "5") (pinfunction "+IN_5") (pintype "input"))
      (node (ref "IC11") (pin "8") (pinfunction "GND_8") (pintype "power_in"))
      (node (ref "IC12") (pin "3") (pinfunction "+IN_3") (pintype "input"))
      (node (ref "IC12") (pin "5") (pinfunction "+IN_5") (pintype "input"))
      (node (ref "IC13") (pin "3") (pinfunction "+IN_3") (pintype "input"))
      (node (ref "IC13") (pin "5") (pinfunction "+IN_5") (pintype "input"))
      (node (ref "IC14") (pin "4") (pinfunction "V-_4") (pintype "power_in"))
      (node (ref "IC2") (pin "1") (pinfunction "C_1") (pintype "passive"))
      (node (ref "IC3") (pin "3") (pinfunction "+IN_3") (pintype "input"))
      (node (ref "IC3") (pin "5") (pinfunction "+IN_5") (pintype "input"))
      (node (ref "IC4") (pin "10") (pinfunction "+IN_10") (pintype "input"))
      (node (ref "IC4") (pin "12") (pinfunction "+IN_12") (pintype "input"))
      (node (ref "IC4") (pin "3") (pinfunction "+IN_3") (pintype "input"))
      (node (ref "IC4") (pin "5") (pinfunction "+IN_5") (pintype "input"))
      (node (ref "IC5") (pin "8") (pinfunction "GND_8") (pintype "power_in"))
      (node (ref "IC6") (pin "10") (pinfunction "+IN_10") (pintype "input"))
      (node (ref "IC6") (pin "12") (pinfunction "+IN_12") (pintype "input"))
      (node (ref "IC6") (pin "3") (pinfunction "+IN_3") (pintype "input"))
      (node (ref "IC6") (pin "5") (pinfunction "+IN_5") (pintype "input"))
      (node (ref "IC7") (pin "10") (pinfunction "+IN_10") (pintype "input"))
      (node (ref "IC7") (pin "12") (pinfunction "+IN_12") (pintype "input"))
      (node (ref "IC7") (pin "3") (pinfunction "+IN_3") (pintype "input"))
      (node (ref "IC7") (pin "5") (pinfunction "+IN_5") (pintype "input"))
      (node (ref "IC8") (pin "8") (pinfunction "GND_8") (pintype "power_in"))
      (node (ref "IC9") (pin "10") (pinfunction "+IN_10") (pintype "input"))
      (node (ref "IC9") (pin "12") (pinfunction "+IN_12") (pintype "input"))
      (node (ref "IC9") (pin "3") (pinfunction "+IN_3") (pintype "input"))
      (node (ref "IC9") (pin "5") (pinfunction "+IN_5") (pintype "input"))
      (node (ref "J1") (pin "P1") (pinfunction "1_P1") (pintype "passive"))
      (node (ref "J10") (pin "P1") (pinfunction "1_P1") (pintype "passive"))
      (node (ref "J11") (pin "P1") (pinfunction "1_P1") (pintype "passive"))
      (node (ref "J12") (pin "P1") (pinfunction "1_P1") (pintype "passive"))
      (node (ref "J13") (pin "P1") (pinfunction "1_P1") (pintype "passive"))
      (node (ref "J14") (pin "P1") (pinfunction "1_P1") (pintype "passive"))
      (node (ref "J2") (pin "P1") (pinfunction "1_P1") (pintype "passive"))
      (node (ref "J3") (pin "P1") (pinfunction "1_P1") (pintype "passive"))
      (node (ref "J4") (pin "P1") (pinfunction "1_P1") (pintype "passive"))
      (node (ref "J5") (pin "P1") (pinfunction "1_P1") (pintype "passive"))
      (node (ref "J6") (pin "P1") (pinfunction "1_P1") (pintype "passive"))
      (node (ref "J7") (pin "P1") (pinfunction "1_P1") (pintype "passive"))
      (node (ref "J8") (pin "P1") (pinfunction "1_P1") (pintype "passive"))
      (node (ref "J9") (pin "P1") (pinfunction "1_P1") (pintype "passive"))
      (node (ref "JP11") (pin "3") (pinfunction "3_3") (pintype "passive"))
      (node (ref "JP11") (pin "4") (pinfunction "4_4") (pintype "passive"))
      (node (ref "JP11") (pin "5") (pinfunction "5_5") (pintype "passive"))
      (node (ref "JP11") (pin "6") (pinfunction "6_6") (pintype "passive"))
      (node (ref "JP11") (pin "7") (pinfunction "7_7") (pintype "passive"))
      (node (ref "JP11") (pin "8") (pinfunction "8_8") (pintype "passive"))
      (node (ref "JP6") (pin "1") (pinfunction "1_1") (pintype "passive"))
      (node (ref "JP6") (pin "2") (pinfunction "2_2") (pintype "passive"))
      (node (ref "JP6") (pin "3") (pinfunction "3_3") (pintype "passive"))
      (node (ref "JP7") (pin "1") (pinfunction "1_1") (pintype "passive"))
      (node (ref "JP7") (pin "2") (pinfunction "2_2") (pintype "passive"))
      (node (ref "JP7") (pin "3") (pinfunction "3_3") (pintype "passive"))
      (node (ref "Q1") (pin "E") (pinfunction "E_E") (pintype "passive"))
      (node (ref "R100") (pin "P$1") (pinfunction "E_P$1") (pintype "passive"))
      (node (ref "R101") (pin "P$1") (pinfunction "E_P$1") (pintype "passive"))
      (node (ref "R116") (pin "1") (pinfunction "1_1") (pintype "passive"))
      (node (ref "R117") (pin "1") (pinfunction "1_1") (pintype "passive"))
      (node (ref "R120") (pin "1") (pinfunction "1_1") (pintype "passive"))
      (node (ref "R3") (pin "P$1") (pinfunction "E_P$1") (pintype "passive"))
      (node (ref "R34") (pin "P$1") (pinfunction "E_P$1") (pintype "passive"))
      (node (ref "R36") (pin "P$1") (pinfunction "E_P$1") (pintype "passive"))
      (node (ref "R4") (pin "P$1") (pinfunction "E_P$1") (pintype "passive"))
      (node (ref "R42") (pin "P$3") (pinfunction "A_P$3") (pintype "passive"))
      (node (ref "R65") (pin "P$3") (pinfunction "A_P$3") (pintype "passive"))
      (node (ref "R68") (pin "P$1") (pinfunction "E_P$1") (pintype "passive"))
      (node (ref "R69") (pin "P$1") (pinfunction "E_P$1") (pintype "passive"))
    )
    (net (code "8") (name "HP_1") (class "Default")
      (node (ref "IC9") (pin "1") (pinfunction "OUT_1") (pintype "output"))
      (node (ref "JP13") (pin "3") (pinfunction "3_3") (pintype "passive"))
      (node (ref "R75") (pin "2") (pinfunction "2_2") (pintype "passive"))
      (node (ref "R86") (pin "1") (pinfunction "1_1") (pintype "passive"))
    )
    (net (code "9") (name "HP_2") (class "Default")
      (node (ref "IC6") (pin "1") (pinfunction "OUT_1") (pintype "output"))
      (node (ref "JP5") (pin "3") (pinfunction "3_3") (pintype "passive"))
      (node (ref "R40") (pin "2") (pinfunction "2_2") (pintype "passive"))
      (node (ref "R52") (pin "1") (pinfunction "1_1") (pintype "passive"))
    )
    (net (code "10") (name "IN") (class "Default")
      (node (ref "IC12") (pin "7") (pinfunction "OUT_7") (pintype "output"))
      (node (ref "JP12") (pin "3") (pinfunction "3_3") (pintype "passive"))
      (node (ref "R103") (pin "2") (pinfunction "2_2") (pintype "passive"))
      (node (ref "R15") (pin "1") (pinfunction "1_1") (pintype "passive"))
      (node (ref "R16") (pin "1") (pinfunction "1_1") (pintype "passive"))
      (node (ref "R17") (pin "1") (pinfunction "1_1") (pintype "passive"))
      (node (ref "R37") (pin "1") (pinfunction "1_1") (pintype "passive"))
      (node (ref "R72") (pin "1") (pinfunction "1_1") (pintype "passive"))
    )
    (net (code "11") (name "MINUS_BUS") (class "Default")
      (node (ref "IC11") (pin "12") (pinfunction "OUT_12") (pintype "output"))
      (node (ref "IC13") (pin "2") (pinfunction "-IN_2") (pintype "input"))
      (node (ref "IC5") (pin "5") (pinfunction "OUT_5") (pintype "output"))
      (node (ref "IC8") (pin "12") (pinfunction "OUT_12") (pintype "output"))
      (node (ref "R104") (pin "2") (pinfunction "2_2") (pintype "passive"))
      (node (ref "R107") (pin "1") (pinfunction "1_1") (pintype "passive"))
      (node (ref "R19") (pin "2") (pinfunction "2_2") (pintype "passive"))
    )
    (net (code "12") (name "Net-(C14-Pad1)") (class "Default")
      (node (ref "C14") (pin "1") (pinfunction "1_1") (pintype "passive"))
      (node (ref "R21") (pin "1") (pinfunction "1_1") (pintype "passive"))
    )
    (net (code "13") (name "Net-(C15-Pad1)") (class "Default")
      (node (ref "C15") (pin "1") (pinfunction "1_1") (pintype "passive"))
      (node (ref "R20") (pin "1") (pinfunction "1_1") (pintype "passive"))
    )
    (net (code "14") (name "Net-(C18-Pad1)") (class "Default")
      (node (ref "C18") (pin "1") (pinfunction "1_1") (pintype "passive"))
      (node (ref "R24") (pin "1") (pinfunction "1_1") (pintype "passive"))
    )
    (net (code "15") (name "Net-(C19-Pad1)") (class "Default")
      (node (ref "C19") (pin "1") (pinfunction "1_1") (pintype "passive"))
      (node (ref "R25") (pin "1") (pinfunction "1_1") (pintype "passive"))
    )
    (net (code "16") (name "Net-(C29-Pad1)") (class "Default")
      (node (ref "C29") (pin "1") (pinfunction "1_1") (pintype "passive"))
      (node (ref "R56") (pin "1") (pinfunction "1_1") (pintype "passive"))
    )
    (net (code "17") (name "Net-(C30-Pad1)") (class "Default")
      (node (ref "C30") (pin "1") (pinfunction "1_1") (pintype "passive"))
      (node (ref "R57") (pin "1") (pinfunction "1_1") (pintype "passive"))
    )
    (net (code "18") (name "Net-(C33-Pad1)") (class "Default")
      (node (ref "C33") (pin "1") (pinfunction "1_1") (pintype "passive"))
      (node (ref "R61") (pin "1") (pinfunction "1_1") (pintype "passive"))
    )
    (net (code "19") (name "Net-(C34-Pad1)") (class "Default")
      (node (ref "C34") (pin "1") (pinfunction "1_1") (pintype "passive"))
      (node (ref "R64") (pin "1") (pinfunction "1_1") (pintype "passive"))
    )
    (net (code "20") (name "Net-(C45-Pad1)") (class "Default")
      (node (ref "C45") (pin "1") (pinfunction "1_1") (pintype "passive"))
      (node (ref "R89") (pin "1") (pinfunction "1_1") (pintype "passive"))
    )
    (net (code "21") (name "Net-(C47-Pad1)") (class "Default")
      (node (ref "C47") (pin "1") (pinfunction "1_1") (pintype "passive"))
      (node (ref "R90") (pin "1") (pinfunction "1_1") (pintype "passive"))
    )
    (net (code "22") (name "Net-(C48-Pad1)") (class "Default")
      (node (ref "C48") (pin "1") (pinfunction "1_1") (pintype "passive"))
      (node (ref "R94") (pin "1") (pinfunction "1_1") (pintype "passive"))
    )
    (net (code "23") (name "Net-(C49-Pad1)") (class "Default")
      (node (ref "C49") (pin "1") (pinfunction "1_1") (pintype "passive"))
      (node (ref "R97") (pin "1") (pinfunction "1_1") (pintype "passive"))
    )
    (net (code "24") (name "Net-(C55-Pad1)") (class "Default")
      (node (ref "C55") (pin "1") (pinfunction "1_1") (pintype "passive"))
      (node (ref "R113") (pin "2") (pinfunction "2_2") (pintype "passive"))
      (node (ref "R114") (pin "1") (pinfunction "1_1") (pintype "passive"))
    )
    (net (code "25") (name "Net-(C57-Pad1)") (class "Default")
      (node (ref "C57") (pin "1") (pinfunction "1_1") (pintype "passive"))
      (node (ref "R115") (pin "1") (pinfunction "1_1") (pintype "passive"))
    )
    (net (code "26") (name "Net-(D2-PadA)") (class "Default")
      (node (ref "D2") (pin "A") (pinfunction "A_A") (pintype "passive"))
      (node (ref "JP11") (pin "1") (pinfunction "1_1") (pintype "passive"))
      (node (ref "JP11") (pin "2") (pinfunction "2_2") (pintype "passive"))
    )
    (net (code "27") (name "Net-(D13-PadC)") (class "Default")
      (node (ref "D13") (pin "C") (pinfunction "C_C") (pintype "passive"))
      (node (ref "D14") (pin "C") (pinfunction "C_C") (pintype "passive"))
      (node (ref "R113") (pin "1") (pinfunction "1_1") (pintype "passive"))
    )
    (net (code "28") (name "Net-(IC3A--IN)") (class "Default")
      (node (ref "C6") (pin "1") (pinfunction "1_1") (pintype "passive"))
      (node (ref "IC3") (pin "2") (pinfunction "-IN_2") (pintype "input"))
      (node (ref "IC5") (pin "4") (pinfunction "OUT_4") (pintype "output"))
    )
    (net (code "29") (name "Net-(IC3A-OUT)") (class "Default")
      (node (ref "C6") (pin "2") (pinfunction "2_2") (pintype "passive"))
      (node (ref "IC3") (pin "1") (pinfunction "OUT_1") (pintype "output"))
      (node (ref "R11") (pin "2") (pinfunction "2_2") (pintype "passive"))
      (node (ref "R32") (pin "1") (pinfunction "1_1") (pintype "passive"))
      (node (ref "R33") (pin "1") (pinfunction "1_1") (pintype "passive"))
    )
    (net (code "30") (name "Net-(IC3B--IN)") (class "Default")
      (node (ref "C7") (pin "1") (pinfunction "1_1") (pintype "passive"))
      (node (ref "IC3") (pin "6") (pinfunction "-IN_6") (pintype "input"))
      (node (ref "IC5") (pin "13") (pinfunction "OUT_13") (pintype "output"))
    )
    (net (code "31") (name "Net-(IC3B-OUT)") (class "Default")
      (node (ref "C7") (pin "2") (pinfunction "2_2") (pintype "passive"))
      (node (ref "IC3") (pin "7") (pinfunction "OUT_7") (pintype "output"))
      (node (ref "R10") (pin "2") (pinfunction "2_2") (pintype "passive"))
      (node (ref "R18") (pin "1") (pinfunction "1_1") (pintype "passive"))
      (node (ref "R19") (pin "1") (pinfunction "1_1") (pintype "passive"))
    )
    (net (code "32") (name "Net-(IC4A--IN)") (class "Default")
      (node (ref "C10") (pin "2") (pinfunction "2_2") (pintype "passive"))
      (node (ref "IC4") (pin "2") (pinfunction "-IN_2") (pintype "input"))
      (node (ref "R13") (pin "1") (pinfunction "1_1") (pintype "passive"))
      (node (ref "R3") (pin "P$3") (pinfunction "A_P$3") (pintype "passive"))
      (node (ref "R6") (pin "2") (pinfunction "2_2") (pintype "passive"))
      (node (ref "R7") (pin "2") (pinfunction "2_2") (pintype "passive"))
    )
    (net (code "33") (name "Net-(IC4A-OUT)") (class "Default")
      (node (ref "C10") (pin "1") (pinfunction "1_1") (pintype "passive"))
      (node (ref "D3") (pin "C") (pinfunction "C_C") (pintype "passive"))
      (node (ref "IC4") (pin "1") (pinfunction "OUT_1") (pintype "output"))
      (node (ref "IC5") (pin "14") (pinfunction "CTRL_14") (pintype "input"))
      (node (ref "R13") (pin "2") (pinfunction "2_2") (pintype "passive"))
    )
    (net (code "34") (name "Net-(IC4B--IN)") (class "Default")
      (node (ref "C16") (pin "2") (pinfunction "2_2") (pintype "passive"))
      (node (ref "IC4") (pin "6") (pinfunction "-IN_6") (pintype "input"))
      (node (ref "R101") (pin "P$3") (pinfunction "A_P$3") (pintype "passive"))
      (node (ref "R22") (pin "1") (pinfunction "1_1") (pintype "passive"))
      (node (ref "R26") (pin "2") (pinfunction "2_2") (pintype "passive"))
      (node (ref "R27") (pin "2") (pinfunction "2_2") (pintype "passive"))
      (node (ref "R28") (pin "2") (pinfunction "2_2") (pintype "passive"))
    )
    (net (code "35") (name "Net-(IC4B-OUT)") (class "Default")
      (node (ref "C16") (pin "1") (pinfunction "1_1") (pintype "passive"))
      (node (ref "D6") (pin "C") (pinfunction "C_C") (pintype "passive"))
      (node (ref "IC4") (pin "7") (pinfunction "OUT_7") (pintype "output"))
      (node (ref "IC5") (pin "6") (pinfunction "CTRL_6") (pintype "input"))
      (node (ref "R22") (pin "2") (pinfunction "2_2") (pintype "passive"))
    )
    (net (code "36") (name "Net-(IC4C--IN)") (class "Default")
      (node (ref "C17") (pin "2") (pinfunction "2_2") (pintype "passive"))
      (node (ref "IC4") (pin "9") (pinfunction "-IN_9") (pintype "input"))
      (node (ref "R23") (pin "1") (pinfunction "1_1") (pintype "passive"))
      (node (ref "R29") (pin "2") (pinfunction "2_2") (pintype "passive"))
      (node (ref "R30") (pin "2") (pinfunction "2_2") (pintype "passive"))
      (node (ref "R31") (pin "2") (pinfunction "2_2") (pintype "passive"))
      (node (ref "R4") (pin "P$3") (pinfunction "A_P$3") (pintype "passive"))
    )
    (net (code "37") (name "Net-(IC4C-OUT)") (class "Default")
      (node (ref "C17") (pin "1") (pinfunction "1_1") (pintype "passive"))
      (node (ref "D5") (pin "C") (pinfunction "C_C") (pintype "passive"))
      (node (ref "IC4") (pin "8") (pinfunction "OUT_8") (pintype "output"))
      (node (ref "IC5") (pin "11") (pinfunction "CTRL_11") (pintype "input"))
      (node (ref "R23") (pin "2") (pinfunction "2_2") (pintype "passive"))
    )
    (net (code "38") (name "Net-(IC4D--IN)") (class "Default")
      (node (ref "C11") (pin "2") (pinfunction "2_2") (pintype "passive"))
      (node (ref "IC4") (pin "13") (pinfunction "-IN_13") (pintype "input"))
      (node (ref "R100") (pin "P$3") (pinfunction "A_P$3") (pintype "passive"))
      (node (ref "R14") (pin "1") (pinfunction "1_1") (pintype "passive"))
      (node (ref "R8") (pin "2") (pinfunction "2_2") (pintype "passive"))
      (node (ref "R9") (pin "2") (pinfunction "2_2") (pintype "passive"))
    )
    (net (code "39") (name "Net-(IC4D-OUT)") (class "Default")
      (node (ref "C11") (pin "1") (pinfunction "1_1") (pintype "passive"))
      (node (ref "D4") (pin "C") (pinfunction "C_C") (pintype "passive"))
      (node (ref "IC4") (pin "14") (pinfunction "OUT_14") (pintype "output"))
      (node (ref "IC5") (pin "3") (pinfunction "CTRL_3") (pintype "input"))
      (node (ref "R14") (pin "2") (pinfunction "2_2") (pintype "passive"))
    )
    (net (code "40") (name "Net-(IC5A-IN)") (class "Default")
      (node (ref "IC5") (pin "2") (pinfunction "IN_2") (pintype "input"))
      (node (ref "R11") (pin "1") (pinfunction "1_1") (pintype "passive"))
      (node (ref "R15") (pin "2") (pinfunction "2_2") (pintype "passive"))
      (node (ref "R20") (pin "2") (pinfunction "2_2") (pintype "passive"))
    )
    (net (code "41") (name "Net-(IC5B-IN)") (class "Default")
      (node (ref "IC5") (pin "7") (pinfunction "IN_7") (pintype "input"))
      (node (ref "R25") (pin "2") (pinfunction "2_2") (pintype "passive"))
      (node (ref "R32") (pin "2") (pinfunction "2_2") (pintype "passive"))
    )
    (net (code "42") (name "Net-(IC5C-IN)") (class "Default")
      (node (ref "IC5") (pin "10") (pinfunction "IN_10") (pintype "input"))
      (node (ref "R17") (pin "2") (pinfunction "2_2") (pintype "passive"))
      (node (ref "R18") (pin "2") (pinfunction "2_2") (pintype "passive"))
      (node (ref "R24") (pin "2") (pinfunction "2_2") (pintype "passive"))
    )
    (net (code "43") (name "Net-(IC5D-IN)") (class "Default")
      (node (ref "IC5") (pin "15") (pinfunction "IN_15") (pintype "input"))
      (node (ref "R10") (pin "1") (pinfunction "1_1") (pintype "passive"))
      (node (ref "R16") (pin "2") (pinfunction "2_2") (pintype "passive"))
      (node (ref "R21") (pin "2") (pinfunction "2_2") (pintype "passive"))
    )
    (net (code "44") (name "Net-(IC6A--IN)") (class "Default")
      (node (ref "IC6") (pin "2") (pinfunction "-IN_2") (pintype "input"))
      (node (ref "R35") (pin "1") (pinfunction "1_1") (pintype "passive"))
      (node (ref "R37") (pin "2") (pinfunction "2_2") (pintype "passive"))
      (node (ref "R38") (pin "1") (pinfunction "1_1") (pintype "passive"))
      (node (ref "R40") (pin "1") (pinfunction "1_1") (pintype "passive"))
    )
    (net (code "45") (name "Net-(IC6B--IN)") (class "Default")
      (node (ref "C25") (pin "1") (pinfunction "1_1") (pintype "passive"))
      (node (ref "IC6") (pin "6") (pinfunction "-IN_6") (pintype "input"))
      (node (ref "IC8") (pin "4") (pinfunction "OUT_4") (pintype "output"))
    )
    (net (code "46") (name "Net-(IC6C--IN)") (class "Default")
      (node (ref "C26") (pin "1") (pinfunction "1_1") (pintype "passive"))
      (node (ref "IC6") (pin "9") (pinfunction "-IN_9") (pintype "input"))
      (node (ref "IC8") (pin "13") (pinfunction "OUT_13") (pintype "output"))
    )
    (net (code "47") (name "Net-(IC6C-OUT)") (class "Default")
      (node (ref "C26") (pin "2") (pinfunction "2_2") (pintype "passive"))
      (node (ref "IC6") (pin "8") (pinfunction "OUT_8") (pintype "output"))
      (node (ref "JP5") (pin "2") (pinfunction "2_2") (pintype "passive"))
      (node (ref "R35") (pin "2") (pinfunction "2_2") (pintype "passive"))
    )
    (net (code "48") (name "Net-(IC6D--IN)") (class "Default")
      (node (ref "IC6") (pin "13") (pinfunction "-IN_13") (pintype "input"))
      (node (ref "IC8") (pin "5") (pinfunction "OUT_5") (pintype "output"))
      (node (ref "R41") (pin "2") (pinfunction "2_2") (pintype "passive"))
    )
    (net (code "49") (name "Net-(IC6D-OUT)") (class "Default")
      (node (ref "IC6") (pin "14") (pinfunction "OUT_14") (pintype "output"))
      (node (ref "R38") (pin "2") (pinfunction "2_2") (pintype "passive"))
      (node (ref "R39") (pin "1") (pinfunction "1_1") (pintype "passive"))
      (node (ref "R55") (pin "1") (pinfunction "1_1") (pintype "passive"))
      (node (ref "R67") (pin "1") (pinfunction "1_1") (pintype "passive"))
    )
    (net (code "50") (name "Net-(IC7A--IN)") (class "Default")
      (node (ref "C23") (pin "2") (pinfunction "2_2") (pintype "passive"))
      (node (ref "IC7") (pin "2") (pinfunction "-IN_2") (pintype "input"))
      (node (ref "R36") (pin "P$3") (pinfunction "A_P$3") (pintype "passive"))
      (node (ref "R44") (pin "2") (pinfunction "2_2") (pintype "passive"))
      (node (ref "R45") (pin "2") (pinfunction "2_2") (pintype "passive"))
      (node (ref "R46") (pin "2") (pinfunction "2_2") (pintype "passive"))
      (node (ref "R50") (pin "1") (pinfunction "1_1") (pintype "passive"))
    )
    (net (code "51") (name "Net-(IC7A-OUT)") (class "Default")
      (node (ref "C23") (pin "1") (pinfunction "1_1") (pintype "passive"))
      (node (ref "D7") (pin "C") (pinfunction "C_C") (pintype "passive"))
      (node (ref "IC7") (pin "1") (pinfunction "OUT_1") (pintype "output"))
      (node (ref "IC8") (pin "11") (pinfunction "CTRL_11") (pintype "input"))
      (node (ref "R50") (pin "2") (pinfunction "2_2") (pintype "passive"))
    )
    (net (code "52") (name "Net-(IC7B--IN)") (class "Default")
      (node (ref "IC7") (pin "6") (pinfunction "-IN_6") (pintype "input"))
      (node (ref "R58") (pin "2") (pinfunction "2_2") (pintype "passive"))
      (node (ref "R59") (pin "1") (pinfunction "1_1") (pintype "passive"))
    )
    (net (code "53") (name "Net-(IC7B-OUT)") (class "Default")
      (node (ref "IC7") (pin "7") (pinfunction "OUT_7") (pintype "output"))
      (node (ref "R59") (pin "2") (pinfunction "2_2") (pintype "passive"))
      (node (ref "R62") (pin "1") (pinfunction "1_1") (pintype "passive"))
    )
    (net (code "54") (name "Net-(IC7C--IN)") (class "Default")
      (node (ref "C32") (pin "2") (pinfunction "2_2") (pintype "passive"))
      (node (ref "IC7") (pin "9") (pinfunction "-IN_9") (pintype "input"))
      (node (ref "R42") (pin "P$1") (pinfunction "E_P$1") (pintype "passive"))
      (node (ref "R60") (pin "1") (pinfunction "1_1") (pintype "passive"))
      (node (ref "R62") (pin "2") (pinfunction "2_2") (pintype "passive"))
      (node (ref "R63") (pin "2") (pinfunction "2_2") (pintype "passive"))
    )
    (net (code "55") (name "Net-(IC7C-OUT)") (class "Default")
      (node (ref "C32") (pin "1") (pinfunction "1_1") (pintype "passive"))
      (node (ref "D9") (pin "C") (pinfunction "C_C") (pintype "passive"))
      (node (ref "IC7") (pin "8") (pinfunction "OUT_8") (pintype "output"))
      (node (ref "IC8") (pin "6") (pinfunction "CTRL_6") (pintype "input"))
      (node (ref "R60") (pin "2") (pinfunction "2_2") (pintype "passive"))
    )
    (net (code "56") (name "Net-(IC7D--IN)") (class "Default")
      (node (ref "C24") (pin "2") (pinfunction "2_2") (pintype "passive"))
      (node (ref "D8") (pin "A") (pinfunction "A_A") (pintype "passive"))
      (node (ref "IC7") (pin "13") (pinfunction "-IN_13") (pintype "input"))
      (node (ref "R34") (pin "P$3") (pinfunction "A_P$3") (pintype "passive"))
      (node (ref "R47") (pin "2") (pinfunction "2_2") (pintype "passive"))
      (node (ref "R48") (pin "2") (pinfunction "2_2") (pintype "passive"))
      (node (ref "R51") (pin "1") (pinfunction "1_1") (pintype "passive"))
    )
    (net (code "57") (name "Net-(IC7D-OUT)") (class "Default")
      (node (ref "D15") (pin "A") (pinfunction "A_A") (pintype "passive"))
      (node (ref "D8") (pin "C") (pinfunction "C_C") (pintype "passive"))
      (node (ref "IC7") (pin "14") (pinfunction "OUT_14") (pintype "output"))
    )
    (net (code "58") (name "Net-(IC8A-CTRL)") (class "Default")
      (node (ref "C24") (pin "1") (pinfunction "1_1") (pintype "passive"))
      (node (ref "D15") (pin "C") (pinfunction "C_C") (pintype "passive"))
      (node (ref "IC8") (pin "14") (pinfunction "CTRL_14") (pintype "input"))
      (node (ref "IC8") (pin "3") (pinfunction "CTRL_3") (pintype "input"))
      (node (ref "R51") (pin "2") (pinfunction "2_2") (pintype "passive"))
    )
    (net (code "59") (name "Net-(IC8A-IN)") (class "Default")
      (node (ref "IC8") (pin "2") (pinfunction "IN_2") (pintype "input"))
      (node (ref "R52") (pin "2") (pinfunction "2_2") (pintype "passive"))
      (node (ref "R56") (pin "2") (pinfunction "2_2") (pintype "passive"))
    )
    (net (code "60") (name "Net-(IC8B-IN)") (class "Default")
      (node (ref "IC8") (pin "7") (pinfunction "IN_7") (pintype "input"))
      (node (ref "R61") (pin "2") (pinfunction "2_2") (pintype "passive"))
      (node (ref "R66") (pin "2") (pinfunction "2_2") (pintype "passive"))
    )
    (net (code "61") (name "Net-(IC8C-IN)") (class "Default")
      (node (ref "IC8") (pin "10") (pinfunction "IN_10") (pintype "input"))
      (node (ref "R64") (pin "2") (pinfunction "2_2") (pintype "passive"))
      (node (ref "R67") (pin "2") (pinfunction "2_2") (pintype "passive"))
    )
    (net (code "62") (name "Net-(IC8D-IN)") (class "Default")
      (node (ref "IC8") (pin "15") (pinfunction "IN_15") (pintype "input"))
      (node (ref "R53") (pin "2") (pinfunction "2_2") (pintype "passive"))
      (node (ref "R57") (pin "2") (pinfunction "2_2") (pintype "passive"))
    )
    (net (code "63") (name "Net-(IC9A--IN)") (class "Default")
      (node (ref "IC9") (pin "2") (pinfunction "-IN_2") (pintype "input"))
      (node (ref "R71") (pin "1") (pinfunction "1_1") (pintype "passive"))
      (node (ref "R72") (pin "2") (pinfunction "2_2") (pintype "passive"))
      (node (ref "R73") (pin "1") (pinfunction "1_1") (pintype "passive"))
      (node (ref "R75") (pin "1") (pinfunction "1_1") (pintype "passive"))
    )
    (net (code "64") (name "Net-(IC9C-OUT)") (class "Default")
      (node (ref "C41") (pin "2") (pinfunction "2_2") (pintype "passive"))
      (node (ref "IC9") (pin "8") (pinfunction "OUT_8") (pintype "output"))
      (node (ref "JP13") (pin "2") (pinfunction "2_2") (pintype "passive"))
      (node (ref "R71") (pin "2") (pinfunction "2_2") (pintype "passive"))
    )
    (net (code "65") (name "Net-(IC9D-OUT)") (class "Default")
      (node (ref "IC9") (pin "14") (pinfunction "OUT_14") (pintype "output"))
      (node (ref "R73") (pin "2") (pinfunction "2_2") (pintype "passive"))
      (node (ref "R74") (pin "1") (pinfunction "1_1") (pintype "passive"))
      (node (ref "R88") (pin "1") (pinfunction "1_1") (pintype "passive"))
      (node (ref "R99") (pin "1") (pinfunction "1_1") (pintype "passive"))
    )
    (net (code "66") (name "Net-(IC10A--IN)") (class "Default")
      (node (ref "C38") (pin "2") (pinfunction "2_2") (pintype "passive"))
      (node (ref "IC10") (pin "2") (pinfunction "-IN_2") (pintype "input"))
      (node (ref "R69") (pin "P$3") (pinfunction "A_P$3") (pintype "passive"))
      (node (ref "R78") (pin "2") (pinfunction "2_2") (pintype "passive"))
      (node (ref "R79") (pin "2") (pinfunction "2_2") (pintype "passive"))
      (node (ref "R80") (pin "2") (pinfunction "2_2") (pintype "passive"))
      (node (ref "R84") (pin "1") (pinfunction "1_1") (pintype "passive"))
    )
    (net (code "67") (name "Net-(IC10A-OUT)") (class "Default")
      (node (ref "C38") (pin "1") (pinfunction "1_1") (pintype "passive"))
      (node (ref "D10") (pin "C") (pinfunction "C_C") (pintype "passive"))
      (node (ref "IC10") (pin "1") (pinfunction "OUT_1") (pintype "output"))
      (node (ref "IC11") (pin "11") (pinfunction "CTRL_11") (pintype "input"))
      (node (ref "R84") (pin "2") (pinfunction "2_2") (pintype "passive"))
    )
    (net (code "68") (name "Net-(IC10B--IN)") (class "Default")
      (node (ref "IC10") (pin "6") (pinfunction "-IN_6") (pintype "input"))
      (node (ref "R91") (pin "2") (pinfunction "2_2") (pintype "passive"))
      (node (ref "R92") (pin "1") (pinfunction "1_1") (pintype "passive"))
    )
    (net (code "69") (name "Net-(IC10B-OUT)") (class "Default")
      (node (ref "IC10") (pin "7") (pinfunction "OUT_7") (pintype "output"))
      (node (ref "R92") (pin "2") (pinfunction "2_2") (pintype "passive"))
      (node (ref "R95") (pin "1") (pinfunction "1_1") (pintype "passive"))
    )
    (net (code "70") (name "Net-(IC10C--IN)") (class "Default")
      (node (ref "C46") (pin "2") (pinfunction "2_2") (pintype "passive"))
      (node (ref "IC10") (pin "9") (pinfunction "-IN_9") (pintype "input"))
      (node (ref "R65") (pin "P$1") (pinfunction "E_P$1") (pintype "passive"))
      (node (ref "R93") (pin "1") (pinfunction "1_1") (pintype "passive"))
      (node (ref "R95") (pin "2") (pinfunction "2_2") (pintype "passive"))
      (node (ref "R96") (pin "2") (pinfunction "2_2") (pintype "passive"))
    )
    (net (code "71") (name "Net-(IC10C-OUT)") (class "Default")
      (node (ref "C46") (pin "1") (pinfunction "1_1") (pintype "passive"))
      (node (ref "D12") (pin "C") (pinfunction "C_C") (pintype "passive"))
      (node (ref "IC10") (pin "8") (pinfunction "OUT_8") (pintype "output"))
      (node (ref "IC11") (pin "6") (pinfunction "CTRL_6") (pintype "input"))
      (node (ref "R93") (pin "2") (pinfunction "2_2") (pintype "passive"))
    )
    (net (code "72") (name "Net-(IC10D--IN)") (class "Default")
      (node (ref "C39") (pin "2") (pinfunction "2_2") (pintype "passive"))
      (node (ref "D11") (pin "A") (pinfunction "A_A") (pintype "passive"))
      (node (ref "IC10") (pin "13") (pinfunction "-IN_13") (pintype "input"))
      (node (ref "R68") (pin "P$3") (pinfunction "A_P$3") (pintype "passive"))
      (node (ref "R81") (pin "2") (pinfunction "2_2") (pintype "passive"))
      (node (ref "R82") (pin "2") (pinfunction "2_2") (pintype "passive"))
      (node (ref "R85") (pin "1") (pinfunction "1_1") (pintype "passive"))
    )
    (net (code "73") (name "Net-(IC10D-OUT)") (class "Default")
      (node (ref "D11") (pin "C") (pinfunction "C_C") (pintype "passive"))
      (node (ref "D16") (pin "A") (pinfunction "A_A") (pintype "passive"))
      (node (ref "IC10") (pin "14") (pinfunction "OUT_14") (pintype "output"))
    )
    (net (code "74") (name "Net-(IC11A-CTRL)") (class "Default")
      (node (ref "C39") (pin "1") (pinfunction "1_1") (pintype "passive"))
      (node (ref "D16") (pin "C") (pinfunction "C_C") (pintype "passive"))
      (node (ref "IC11") (pin "14") (pinfunction "CTRL_14") (pintype "input"))
      (node (ref "IC11") (pin "3") (pinfunction "CTRL_3") (pintype "input"))
      (node (ref "R85") (pin "2") (pinfunction "2_2") (pintype "passive"))
    )
    (net (code "75") (name "Net-(IC11A-IN)") (class "Default")
      (node (ref "IC11") (pin "2") (pinfunction "IN_2") (pintype "input"))
      (node (ref "R86") (pin "2") (pinfunction "2_2") (pintype "passive"))
      (node (ref "R89") (pin "2") (pinfunction "2_2") (pintype "passive"))
    )
    (net (code "76") (name "Net-(IC11A-OUT)") (class "Default")
      (node (ref "C40") (pin "1") (pinfunction "1_1") (pintype "passive"))
      (node (ref "IC11") (pin "4") (pinfunction "OUT_4") (pintype "output"))
      (node (ref "IC9") (pin "6") (pinfunction "-IN_6") (pintype "input"))
    )
    (net (code "77") (name "Net-(IC11B-IN)") (class "Default")
      (node (ref "IC11") (pin "7") (pinfunction "IN_7") (pintype "input"))
      (node (ref "R94") (pin "2") (pinfunction "2_2") (pintype "passive"))
      (node (ref "R98") (pin "2") (pinfunction "2_2") (pintype "passive"))
    )
    (net (code "78") (name "Net-(IC11B-OUT)") (class "Default")
      (node (ref "IC11") (pin "5") (pinfunction "OUT_5") (pintype "output"))
      (node (ref "IC9") (pin "13") (pinfunction "-IN_13") (pintype "input"))
      (node (ref "R76") (pin "2") (pinfunction "2_2") (pintype "passive"))
    )
    (net (code "79") (name "Net-(IC11C-IN)") (class "Default")
      (node (ref "IC11") (pin "10") (pinfunction "IN_10") (pintype "input"))
      (node (ref "R97") (pin "2") (pinfunction "2_2") (pintype "passive"))
      (node (ref "R99") (pin "2") (pinfunction "2_2") (pintype "passive"))
    )
    (net (code "80") (name "Net-(IC11D-IN)") (class "Default")
      (node (ref "IC11") (pin "15") (pinfunction "IN_15") (pintype "input"))
      (node (ref "R87") (pin "2") (pinfunction "2_2") (pintype "passive"))
      (node (ref "R90") (pin "2") (pinfunction "2_2") (pintype "passive"))
    )
    (net (code "81") (name "Net-(IC11D-OUT)") (class "Default")
      (node (ref "C41") (pin "1") (pinfunction "1_1") (pintype "passive"))
      (node (ref "IC11") (pin "13") (pinfunction "OUT_13") (pintype "output"))
      (node (ref "IC9") (pin "9") (pinfunction "-IN_9") (pintype "input"))
    )
    (net (code "82") (name "Net-(IC12A--IN)") (class "Default")
      (node (ref "IC12") (pin "2") (pinfunction "-IN_2") (pintype "input"))
      (node (ref "R102") (pin "1") (pinfunction "1_1") (pintype "passive"))
      (node (ref "R105") (pin "2") (pinfunction "2_2") (pintype "passive"))
    )
    (net (code "83") (name "Net-(IC12A-OUT)") (class "Default")
      (node (ref "IC12") (pin "1") (pinfunction "OUT_1") (pintype "output"))
      (node (ref "R102") (pin "2") (pinfunction "2_2") (pintype "passive"))
      (node (ref "R106") (pin "1") (pinfunction "1_1") (pintype "passive"))
    )
    (net (code "84") (name "Net-(IC12B--IN)") (class "Default")
      (node (ref "IC12") (pin "6") (pinfunction "-IN_6") (pintype "input"))
      (node (ref "R103") (pin "1") (pinfunction "1_1") (pintype "passive"))
      (node (ref "R106") (pin "2") (pinfunction "2_2") (pintype "passive"))
      (node (ref "R122") (pin "1") (pinfunction "1_1") (pintype "passive"))
    )
    (net (code "85") (name "Net-(IC13B-OUT)") (class "Default")
      (node (ref "IC13") (pin "7") (pinfunction "OUT_7") (pintype "output"))
      (node (ref "R104") (pin "1") (pinfunction "1_1") (pintype "passive"))
      (node (ref "R110") (pin "2") (pinfunction "2_2") (pintype "passive"))
    )
    (net (code "86") (name "Net-(IC14A-+IN)") (class "Default")
      (node (ref "IC14") (pin "3") (pinfunction "+IN_3") (pintype "input"))
      (node (ref "IC14") (pin "6") (pinfunction "-IN_6") (pintype "input"))
      (node (ref "R115") (pin "2") (pinfunction "2_2") (pintype "passive"))
      (node (ref "R117") (pin "2") (pinfunction "2_2") (pintype "passive"))
      (node (ref "R118") (pin "1") (pinfunction "1_1") (pintype "passive"))
    )
    (net (code "87") (name "Net-(IC14A--IN)") (class "Default")
      (node (ref "IC14") (pin "2") (pinfunction "-IN_2") (pintype "input"))
      (node (ref "R119") (pin "2") (pinfunction "2_2") (pintype "passive"))
      (node (ref "R121") (pin "1") (pinfunction "1_1") (pintype "passive"))
    )
    (net (code "88") (name "Net-(IC14A-OUT)") (class "Default")
      (node (ref "D13") (pin "A") (pinfunction "A_A") (pintype "passive"))
      (node (ref "IC14") (pin "1") (pinfunction "OUT_1") (pintype "output"))
    )
    (net (code "89") (name "Net-(IC14B-+IN)") (class "Default")
      (node (ref "IC14") (pin "5") (pinfunction "+IN_5") (pintype "input"))
      (node (ref "R119") (pin "1") (pinfunction "1_1") (pintype "passive"))
      (node (ref "R120") (pin "2") (pinfunction "2_2") (pintype "passive"))
    )
    (net (code "90") (name "Net-(IC14B-OUT)") (class "Default")
      (node (ref "D14") (pin "A") (pinfunction "A_A") (pintype "passive"))
      (node (ref "IC14") (pin "7") (pinfunction "OUT_7") (pintype "output"))
    )
    (net (code "91") (name "Net-(J1-3)") (class "Default")
      (node (ref "J1") (pin "P3") (pinfunction "3_P3") (pintype "passive"))
      (node (ref "R6") (pin "1") (pinfunction "1_1") (pintype "passive"))
    )
    (net (code "92") (name "Net-(J2-3)") (class "Default")
      (node (ref "J2") (pin "P3") (pinfunction "3_P3") (pintype "passive"))
      (node (ref "R30") (pin "1") (pinfunction "1_1") (pintype "passive"))
    )
    (net (code "93") (name "Net-(J3-3)") (class "Default")
      (node (ref "J3") (pin "P3") (pinfunction "3_P3") (pintype "passive"))
      (node (ref "R48") (pin "1") (pinfunction "1_1") (pintype "passive"))
    )
    (net (code "94") (name "Net-(J4-3)") (class "Default")
      (node (ref "J4") (pin "P3") (pinfunction "3_P3") (pintype "passive"))
      (node (ref "R45") (pin "1") (pinfunction "1_1") (pintype "passive"))
    )
    (net (code "95") (name "Net-(J5-3)") (class "Default")
      (node (ref "J5") (pin "P3") (pinfunction "3_P3") (pintype "passive"))
      (node (ref "R58") (pin "1") (pinfunction "1_1") (pintype "passive"))
    )
    (net (code "96") (name "Net-(J6-3)") (class "Default")
      (node (ref "J6") (pin "P3") (pinfunction "3_P3") (pintype "passive"))
      (node (ref "R91") (pin "1") (pinfunction "1_1") (pintype "passive"))
    )
    (net (code "97") (name "Net-(J7-3)") (class "Default")
      (node (ref "J7") (pin "P3") (pinfunction "3_P3") (pintype "passive"))
      (node (ref "R82") (pin "1") (pinfunction "1_1") (pintype "passive"))
    )
    (net (code "98") (name "Net-(J8-3)") (class "Default")
      (node (ref "J8") (pin "P3") (pinfunction "3_P3") (pintype "passive"))
      (node (ref "R78") (pin "1") (pinfunction "1_1") (pintype "passive"))
    )
    (net (code "99") (name "Net-(J9-3)") (class "Default")
      (node (ref "J9") (pin "P3") (pinfunction "3_P3") (pintype "passive"))
      (node (ref "R9") (pin "1") (pinfunction "1_1") (pintype "passive"))
    )
    (net (code "100") (name "Net-(J10-3)") (class "Default")
      (node (ref "J10") (pin "P3") (pinfunction "3_P3") (pintype "passive"))
      (node (ref "R27") (pin "1") (pinfunction "1_1") (pintype "passive"))
    )
    (net (code "101") (name "Net-(J13-3)") (class "Default")
      (node (ref "J13") (pin "P3") (pinfunction "3_P3") (pintype "passive"))
      (node (ref "R105") (pin "1") (pinfunction "1_1") (pintype "passive"))
    )
    (net (code "102") (name "Net-(J14-3)") (class "Default")
      (node (ref "J14") (pin "P3") (pinfunction "3_P3") (pintype "passive"))
      (node (ref "R111") (pin "2") (pinfunction "2_2") (pintype "passive"))
    )
    (net (code "103") (name "Net-(JP11-Pad10)") (class "Default")
      (node (ref "JP11") (pin "10") (pinfunction "10_10") (pintype "passive"))
      (node (ref "JP11") (pin "9") (pinfunction "9_9") (pintype "passive"))
      (node (ref "P1") (pin "2") (pinfunction "2_2") (pintype "bidirectional"))
    )
    (net (code "104") (name "Net-(JP12-Pad2)") (class "Default")
      (node (ref "JP12") (pin "2") (pinfunction "2_2") (pintype "passive"))
      (node (ref "R122") (pin "2") (pinfunction "2_2") (pintype "passive"))
    )
    (net (code "105") (name "Net-(LED1-C)") (class "Default")
      (node (ref "LED1") (pin "K") (pinfunction "C_K") (pintype "passive"))
      (node (ref "Q1") (pin "C") (pinfunction "C_C") (pintype "passive"))
    )
    (net (code "106") (name "Net-(LED1-PadA)") (class "Default")
      (node (ref "LED1") (pin "A") (pinfunction "A_A") (pintype "passive"))
      (node (ref "R112") (pin "1") (pinfunction "1_1") (pintype "passive"))
    )
    (net (code "107") (name "Net-(Q1-PadB)") (class "Default")
      (node (ref "Q1") (pin "B") (pinfunction "B_B") (pintype "passive"))
      (node (ref "R114") (pin "2") (pinfunction "2_2") (pintype "passive"))
      (node (ref "R116") (pin "2") (pinfunction "2_2") (pintype "passive"))
    )
    (net (code "108") (name "Net-(R3-S)") (class "Default")
      (node (ref "R3") (pin "P$2") (pinfunction "S_P$2") (pintype "passive"))
      (node (ref "R5") (pin "2") (pinfunction "2_2") (pintype "passive"))
    )
    (net (code "109") (name "Net-(R4-S)") (class "Default")
      (node (ref "R12") (pin "2") (pinfunction "2_2") (pintype "passive"))
      (node (ref "R4") (pin "P$2") (pinfunction "S_P$2") (pintype "passive"))
    )
    (net (code "110") (name "Net-(R34-S)") (class "Default")
      (node (ref "R34") (pin "P$2") (pinfunction "S_P$2") (pintype "passive"))
      (node (ref "R43") (pin "2") (pinfunction "2_2") (pintype "passive"))
    )
    (net (code "111") (name "Net-(R36-S)") (class "Default")
      (node (ref "R36") (pin "P$2") (pinfunction "S_P$2") (pintype "passive"))
      (node (ref "R49") (pin "2") (pinfunction "2_2") (pintype "passive"))
    )
    (net (code "112") (name "Net-(R39-Pad2)") (class "Default")
      (node (ref "R39") (pin "2") (pinfunction "2_2") (pintype "passive"))
      (node (ref "R41") (pin "1") (pinfunction "1_1") (pintype "passive"))
    )
    (net (code "113") (name "Net-(R42-S)") (class "Default")
      (node (ref "R42") (pin "P$2") (pinfunction "S_P$2") (pintype "passive"))
      (node (ref "R54") (pin "2") (pinfunction "2_2") (pintype "passive"))
    )
    (net (code "114") (name "Net-(R65-S)") (class "Default")
      (node (ref "R65") (pin "P$2") (pinfunction "S_P$2") (pintype "passive"))
      (node (ref "R70") (pin "2") (pinfunction "2_2") (pintype "passive"))
    )
    (net (code "115") (name "Net-(R68-S)") (class "Default")
      (node (ref "R68") (pin "P$2") (pinfunction "S_P$2") (pintype "passive"))
      (node (ref "R77") (pin "2") (pinfunction "2_2") (pintype "passive"))
    )
    (net (code "116") (name "Net-(R69-S)") (class "Default")
      (node (ref "R69") (pin "P$2") (pinfunction "S_P$2") (pintype "passive"))
      (node (ref "R83") (pin "2") (pinfunction "2_2") (pintype "passive"))
    )
    (net (code "117") (name "Net-(R74-Pad2)") (class "Default")
      (node (ref "R74") (pin "2") (pinfunction "2_2") (pintype "passive"))
      (node (ref "R76") (pin "1") (pinfunction "1_1") (pintype "passive"))
    )
    (net (code "118") (name "Net-(R100-S)") (class "Default")
      (node (ref "R100") (pin "P$2") (pinfunction "S_P$2") (pintype "passive"))
      (node (ref "R109") (pin "2") (pinfunction "2_2") (pintype "passive"))
    )
    (net (code "119") (name "Net-(R101-S)") (class "Default")
      (node (ref "R101") (pin "P$2") (pinfunction "S_P$2") (pintype "passive"))
      (node (ref "R108") (pin "2") (pinfunction "2_2") (pintype "passive"))
    )
    (net (code "120") (name "OUTPUT") (class "Default")
      (node (ref "C57") (pin "2") (pinfunction "2_2") (pintype "passive"))
      (node (ref "IC13") (pin "1") (pinfunction "OUT_1") (pintype "output"))
      (node (ref "R107") (pin "2") (pinfunction "2_2") (pintype "passive"))
      (node (ref "R111") (pin "1") (pinfunction "1_1") (pintype "passive"))
    )
    (net (code "121") (name "PLUS_BUS") (class "Default")
      (node (ref "IC13") (pin "6") (pinfunction "-IN_6") (pintype "input"))
      (node (ref "IC5") (pin "12") (pinfunction "OUT_12") (pintype "output"))
      (node (ref "R110") (pin "1") (pinfunction "1_1") (pintype "passive"))
      (node (ref "R33") (pin "2") (pinfunction "2_2") (pintype "passive"))
      (node (ref "R55") (pin "2") (pinfunction "2_2") (pintype "passive"))
      (node (ref "R88") (pin "2") (pinfunction "2_2") (pintype "passive"))
    )
    (net (code "122") (name "VCC") (class "Default")
      (node (ref "C1") (pin "+") (pinfunction "+_+") (pintype "passive"))
      (node (ref "C12") (pin "1") (pinfunction "1_1") (pintype "passive"))
      (node (ref "C21") (pin "1") (pinfunction "1_1") (pintype "passive"))
      (node (ref "C27") (pin "1") (pinfunction "1_1") (pintype "passive"))
      (node (ref "C31") (pin "1") (pinfunction "1_1") (pintype "passive"))
      (node (ref "C36") (pin "1") (pinfunction "1_1") (pintype "passive"))
      (node (ref "C42") (pin "1") (pinfunction "1_1") (pintype "passive"))
      (node (ref "C43") (pin "1") (pinfunction "1_1") (pintype "passive"))
      (node (ref "C5") (pin "1") (pinfunction "1_1") (pintype "passive"))
      (node (ref "C50") (pin "1") (pinfunction "1_1") (pintype "passive"))
      (node (ref "C52") (pin "1") (pinfunction "1_1") (pintype "passive"))
      (node (ref "C56") (pin "1") (pinfunction "1_1") (pintype "passive"))
      (node (ref "C58") (pin "+") (pinfunction "+_+") (pintype "passive"))
      (node (ref "C9") (pin "1") (pinfunction "1_1") (pintype "passive"))
      (node (ref "D2") (pin "C") (pinfunction "C_C") (pintype "passive"))
      (node (ref "IC10") (pin "4") (pinfunction "V+_4") (pintype "power_in"))
      (node (ref "IC11") (pin "16") (pinfunction "V+_16") (pintype "power_in"))
      (node (ref "IC12") (pin "8") (pinfunction "V+_8") (pintype "power_in"))
      (node (ref "IC13") (pin "8") (pinfunction "V+_8") (pintype "power_in"))
      (node (ref "IC14") (pin "8") (pinfunction "V+_8") (pintype "power_in"))
      (node (ref "IC3") (pin "8") (pinfunction "V+_8") (pintype "power_in"))
      (node (ref "IC4") (pin "4") (pinfunction "V+_4") (pintype "power_in"))
      (node (ref "IC5") (pin "16") (pinfunction "V+_16") (pintype "power_in"))
      (node (ref "IC6") (pin "4") (pinfunction "V+_4") (pintype "power_in"))
      (node (ref "IC7") (pin "4") (pinfunction "V+_4") (pintype "power_in"))
      (node (ref "IC8") (pin "16") (pinfunction "V+_16") (pintype "power_in"))
      (node (ref "IC9") (pin "4") (pinfunction "V+_4") (pintype "power_in"))
      (node (ref "R1") (pin "1") (pinfunction "1_1") (pintype "passive"))
      (node (ref "R112") (pin "2") (pinfunction "2_2") (pintype "passive"))
    )
    (net (code "123") (name "VEE") (class "Default")
      (node (ref "C13") (pin "2") (pinfunction "2_2") (pintype "passive"))
      (node (ref "C2") (pin "-") (pinfunction "-_-") (pintype "passive"))
      (node (ref "C20") (pin "2") (pinfunction "2_2") (pintype "passive"))
      (node (ref "C22") (pin "2") (pinfunction "2_2") (pintype "passive"))
      (node (ref "C28") (pin "2") (pinfunction "2_2") (pintype "passive"))
      (node (ref "C35") (pin "2") (pinfunction "2_2") (pintype "passive"))
      (node (ref "C37") (pin "2") (pinfunction "2_2") (pintype "passive"))
      (node (ref "C44") (pin "2") (pinfunction "2_2") (pintype "passive"))
      (node (ref "C51") (pin "2") (pinfunction "2_2") (pintype "passive"))
      (node (ref "C53") (pin "2") (pinfunction "2_2") (pintype "passive"))
      (node (ref "C54") (pin "2") (pinfunction "2_2") (pintype "passive"))
      (node (ref "C8") (pin "2") (pinfunction "2_2") (pintype "passive"))
      (node (ref "D1") (pin "A") (pinfunction "A_A") (pintype "passive"))
      (node (ref "IC10") (pin "11") (pinfunction "V-_11") (pintype "power_in"))
      (node (ref "IC11") (pin "9") (pinfunction "V-_9") (pintype "power_in"))
      (node (ref "IC12") (pin "4") (pinfunction "V-_4") (pintype "power_in"))
      (node (ref "IC13") (pin "4") (pinfunction "V-_4") (pintype "power_in"))
      (node (ref "IC3") (pin "4") (pinfunction "V-_4") (pintype "power_in"))
      (node (ref "IC4") (pin "11") (pinfunction "V-_11") (pintype "power_in"))
      (node (ref "IC5") (pin "9") (pinfunction "V-_9") (pintype "power_in"))
      (node (ref "IC6") (pin "11") (pinfunction "V-_11") (pintype "power_in"))
      (node (ref "IC7") (pin "11") (pinfunction "V-_11") (pintype "power_in"))
      (node (ref "IC8") (pin "9") (pinfunction "V-_9") (pintype "power_in"))
      (node (ref "IC9") (pin "11") (pinfunction "V-_11") (pintype "power_in"))
      (node (ref "P1") (pin "1") (pinfunction "1_1") (pintype "bidirectional"))
      (node (ref "R2") (pin "1") (pinfunction "1_1") (pintype "passive"))
    )
    (net (code "124") (name "unconnected-(IC5E-MODE-Pad1)") (class "Default")
      (node (ref "IC5") (pin "1") (pinfunction "MODE_1") (pintype "input"))
    )
    (net (code "125") (name "unconnected-(IC8E-MODE-Pad1)") (class "Default")
      (node (ref "IC8") (pin "1") (pinfunction "MODE_1") (pintype "input"))
    )
    (net (code "126") (name "unconnected-(IC11E-MODE-Pad1)") (class "Default")
      (node (ref "IC11") (pin "1") (pinfunction "MODE_1") (pintype "input"))
    )
    (net (code "127") (name "unconnected-(J1-2-PadP2)") (class "Default")
      (node (ref "J1") (pin "P2") (pinfunction "2_P2") (pintype "passive"))
    )
    (net (code "128") (name "unconnected-(J2-2-PadP2)") (class "Default")
      (node (ref "J2") (pin "P2") (pinfunction "2_P2") (pintype "passive"))
    )
    (net (code "129") (name "unconnected-(J3-2-PadP2)") (class "Default")
      (node (ref "J3") (pin "P2") (pinfunction "2_P2") (pintype "passive"))
    )
    (net (code "130") (name "unconnected-(J4-2-PadP2)") (class "Default")
      (node (ref "J4") (pin "P2") (pinfunction "2_P2") (pintype "passive"))
    )
    (net (code "131") (name "unconnected-(J5-2-PadP2)") (class "Default")
      (node (ref "J5") (pin "P2") (pinfunction "2_P2") (pintype "passive"))
    )
    (net (code "132") (name "unconnected-(J6-2-PadP2)") (class "Default")
      (node (ref "J6") (pin "P2") (pinfunction "2_P2") (pintype "passive"))
    )
    (net (code "133") (name "unconnected-(J7-2-PadP2)") (class "Default")
      (node (ref "J7") (pin "P2") (pinfunction "2_P2") (pintype "passive"))
    )
    (net (code "134") (name "unconnected-(J8-2-PadP2)") (class "Default")
      (node (ref "J8") (pin "P2") (pinfunction "2_P2") (pintype "passive"))
    )
    (net (code "135") (name "unconnected-(J9-2-PadP2)") (class "Default")
      (node (ref "J9") (pin "P2") (pinfunction "2_P2") (pintype "passive"))
    )
    (net (code "136") (name "unconnected-(J10-2-PadP2)") (class "Default")
      (node (ref "J10") (pin "P2") (pinfunction "2_P2") (pintype "passive"))
    )
    (net (code "137") (name "unconnected-(J11-2-PadP2)") (class "Default")
      (node (ref "J11") (pin "P2") (pinfunction "2_P2") (pintype "passive"))
    )
    (net (code "138") (name "unconnected-(J12-2-PadP2)") (class "Default")
      (node (ref "J12") (pin "P2") (pinfunction "2_P2") (pintype "passive"))
    )
    (net (code "139") (name "unconnected-(J13-2-PadP2)") (class "Default")
      (node (ref "J13") (pin "P2") (pinfunction "2_P2") (pintype "passive"))
    )
    (net (code "140") (name "unconnected-(J14-2-PadP2)") (class "Default")
      (node (ref "J14") (pin "P2") (pinfunction "2_P2") (pintype "passive"))
    )
    (net (code "141") (name "unconnected-(JP12-Pad1)") (class "Default")
      (node (ref "JP12") (pin "1") (pinfunction "1_1") (pintype "passive"))
    )
  )
)
